# DashCam_Schematic.net
KiCad netlist of a schematic drawn in EAGLE
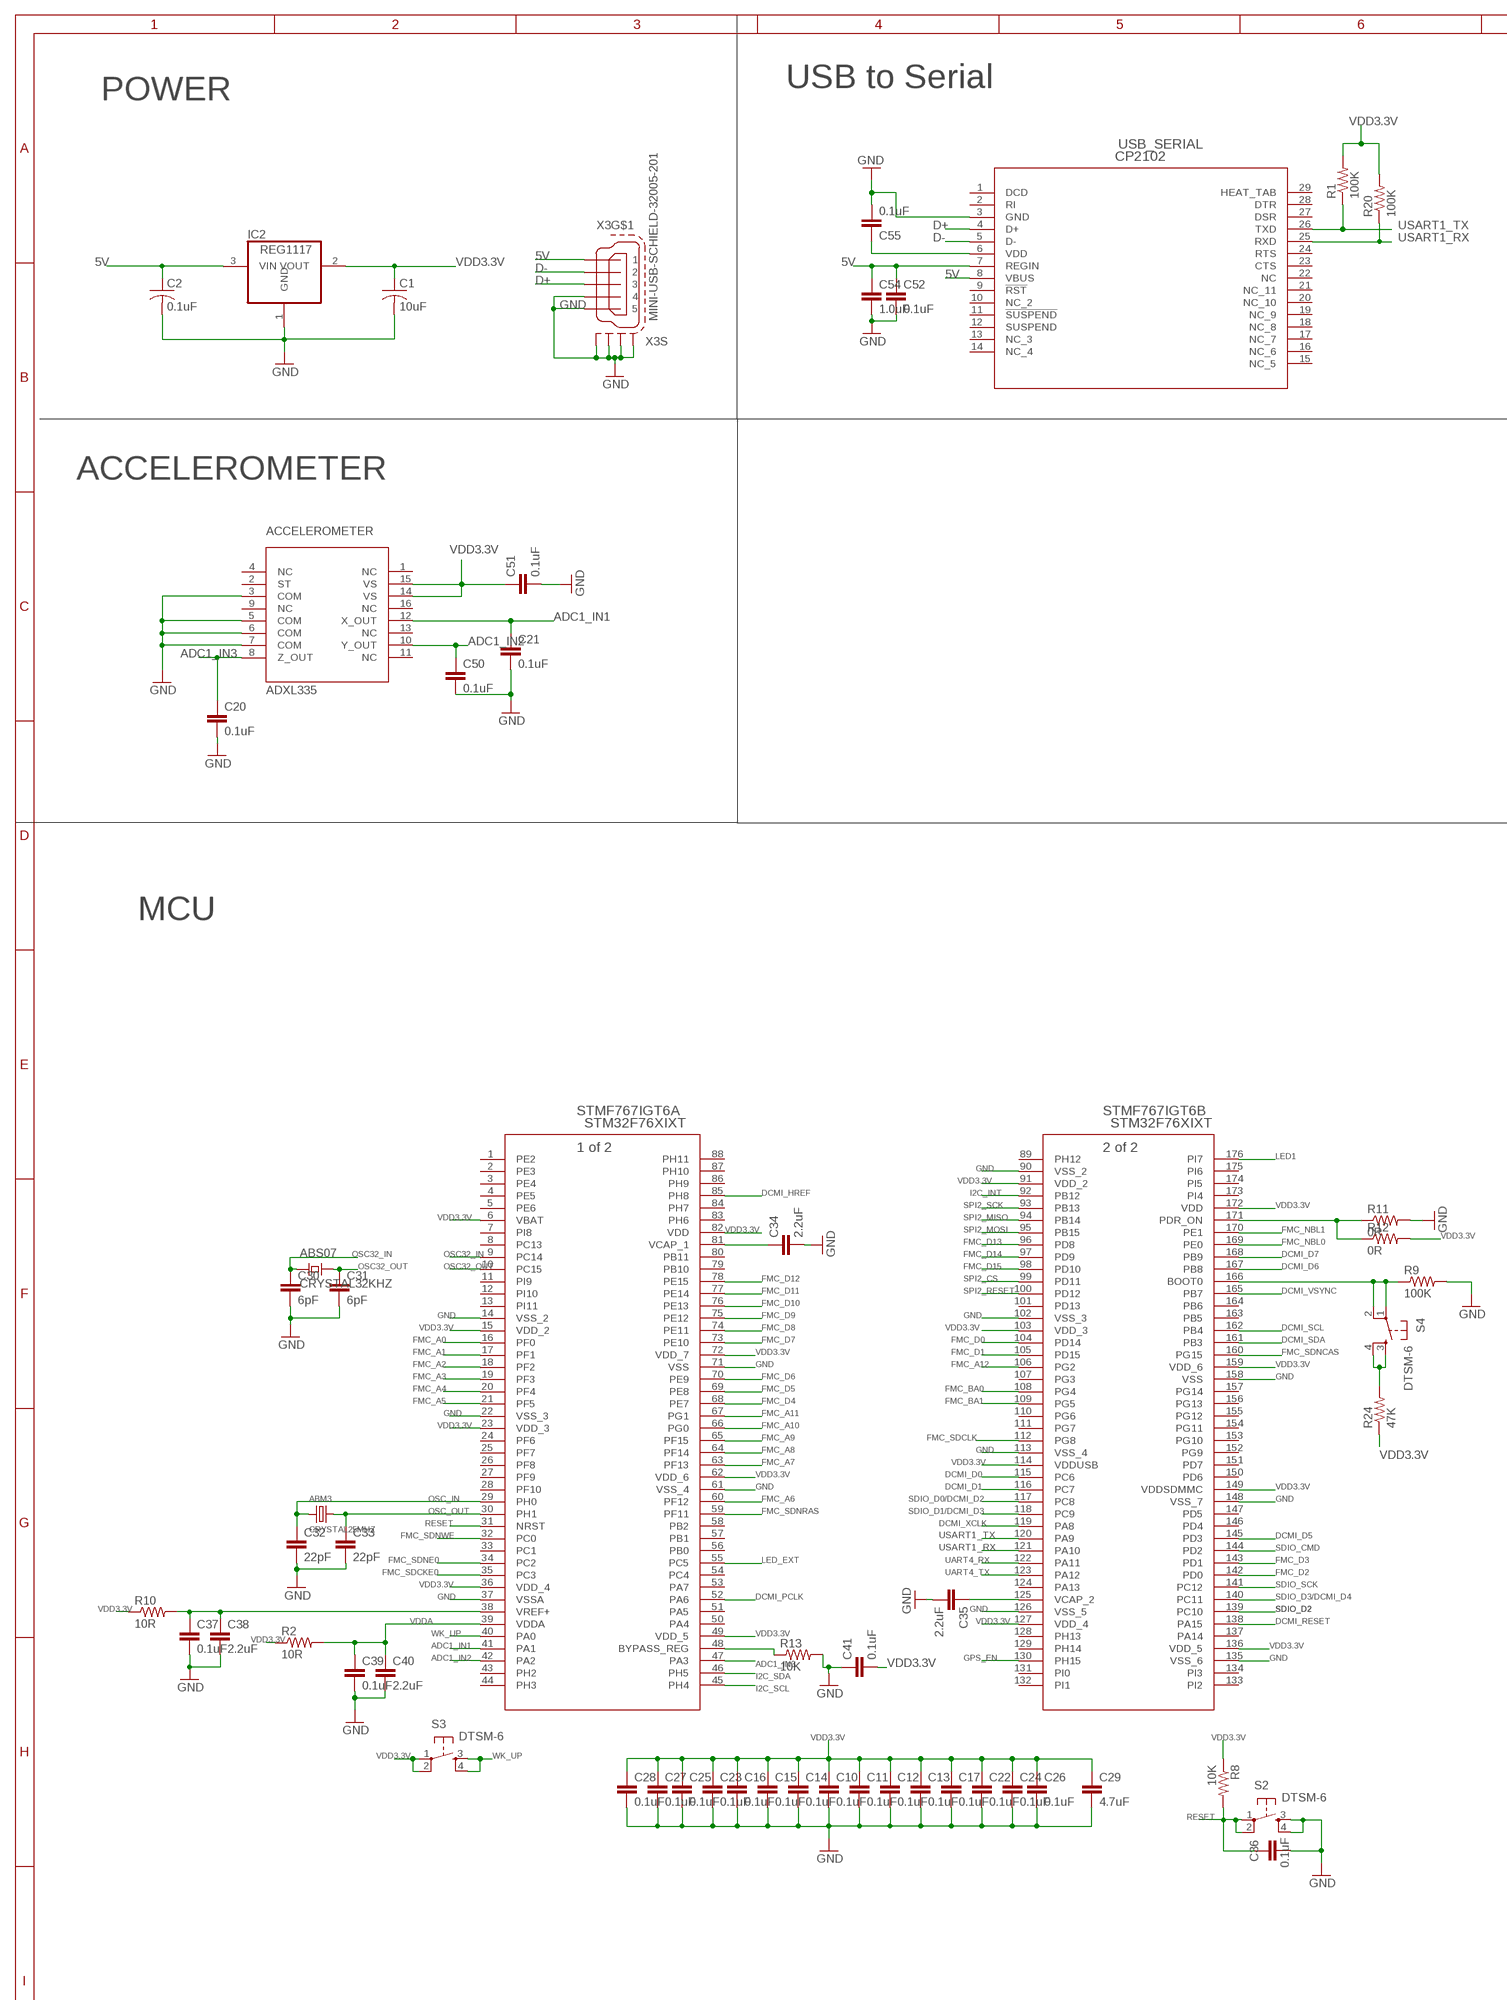
[diagram p0: schematic, sheet 1, part 1 of 2]
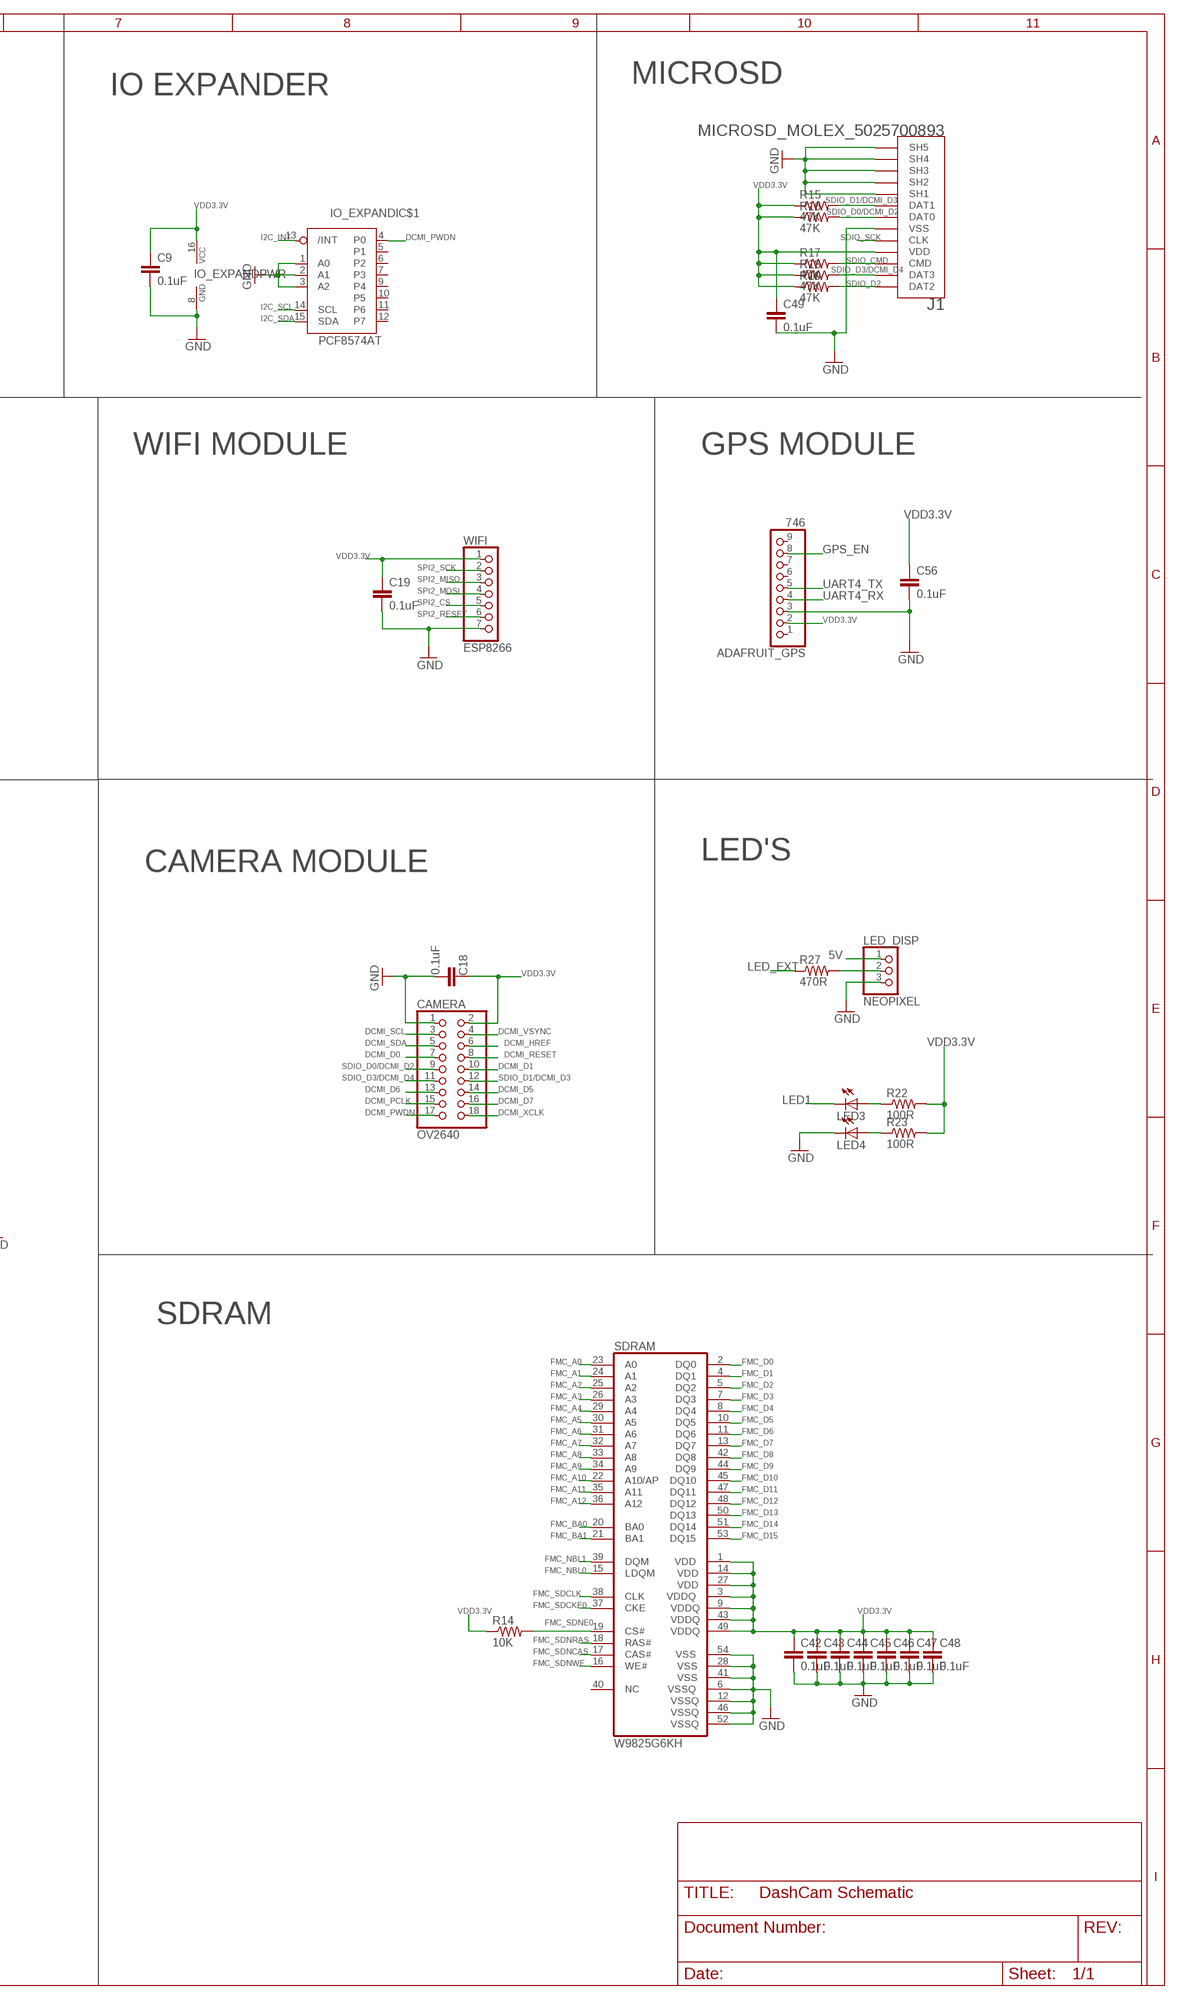
[diagram p1: schematic, sheet 1, part 2 of 2]

(export (version "E")
  (design (tool "Eeschema 10.0.6"))
  (components
    (comp (ref "ABM3")
      (value "CRYSTAL25MHZ")
      (footprint "eagle-import:6X3.3MM")
      (libsource (lib "eagle-import") (part "CRYSTAL.6X3.3MM"))
    )
    (comp (ref "ABS07")
      (value "CRYSTAL32KHZ")
      (footprint "eagle-import:2-SMD_ABM7")
      (libsource (lib "eagle-import") (part "ABSO7"))
    )
    (comp (ref "ACCELEROMETER")
      (value "ADXL335")
      (footprint "eagle-import:LFCSP16")
      (libsource (lib "eagle-import") (part "ADXL335"))
    )
    (comp (ref "ADAFRUIT_GPS")
      (value "746")
      (footprint "eagle-import:1X09")
      (libsource (lib "eagle-import") (part "PINHD-1X9"))
    )
    (comp (ref "C1")
      (value "10uF")
      (footprint "eagle-import:C0805")
      (libsource (lib "eagle-import") (part "C-USC0805"))
    )
    (comp (ref "C2")
      (value "0.1uF")
      (footprint "eagle-import:C0402")
      (libsource (lib "eagle-import") (part "C-USC0402"))
    )
    (comp (ref "C9")
      (value "0.1uF")
      (footprint "eagle-import:C0402")
      (libsource (lib "eagle-import") (part "C-EUC0402"))
    )
    (comp (ref "C10")
      (value "0.1uF")
      (footprint "eagle-import:C0402")
      (libsource (lib "eagle-import") (part "C-EUC0402"))
    )
    (comp (ref "C11")
      (value "0.1uF")
      (footprint "eagle-import:C0402")
      (libsource (lib "eagle-import") (part "C-EUC0402"))
    )
    (comp (ref "C12")
      (value "0.1uF")
      (footprint "eagle-import:C0402")
      (libsource (lib "eagle-import") (part "C-EUC0402"))
    )
    (comp (ref "C13")
      (value "0.1uF")
      (footprint "eagle-import:C0402")
      (libsource (lib "eagle-import") (part "C-EUC0402"))
    )
    (comp (ref "C14")
      (value "0.1uF")
      (footprint "eagle-import:C0402")
      (libsource (lib "eagle-import") (part "C-EUC0402"))
    )
    (comp (ref "C15")
      (value "0.1uF")
      (footprint "eagle-import:C0402")
      (libsource (lib "eagle-import") (part "C-EUC0402"))
    )
    (comp (ref "C16")
      (value "0.1uF")
      (footprint "eagle-import:C0402")
      (libsource (lib "eagle-import") (part "C-EUC0402"))
    )
    (comp (ref "C17")
      (value "0.1uF")
      (footprint "eagle-import:C0402")
      (libsource (lib "eagle-import") (part "C-EUC0402"))
    )
    (comp (ref "C18")
      (value "0.1uF")
      (footprint "eagle-import:C0402")
      (libsource (lib "eagle-import") (part "C-EUC0402"))
    )
    (comp (ref "C19")
      (value "0.1uF")
      (footprint "eagle-import:C0402")
      (libsource (lib "eagle-import") (part "C-EUC0402"))
    )
    (comp (ref "C20")
      (value "0.1uF")
      (footprint "eagle-import:C0402")
      (libsource (lib "eagle-import") (part "C-EUC0402"))
    )
    (comp (ref "C21")
      (value "0.1uF")
      (footprint "eagle-import:C0402")
      (libsource (lib "eagle-import") (part "C-EUC0402"))
    )
    (comp (ref "C22")
      (value "0.1uF")
      (footprint "eagle-import:C0402")
      (libsource (lib "eagle-import") (part "C-EUC0402"))
    )
    (comp (ref "C23")
      (value "0.1uF")
      (footprint "eagle-import:C0402")
      (libsource (lib "eagle-import") (part "C-EUC0402"))
    )
    (comp (ref "C24")
      (value "0.1uF")
      (footprint "eagle-import:C0402")
      (libsource (lib "eagle-import") (part "C-EUC0402"))
    )
    (comp (ref "C25")
      (value "0.1uF")
      (footprint "eagle-import:C0402")
      (libsource (lib "eagle-import") (part "C-EUC0402"))
    )
    (comp (ref "C26")
      (value "0.1uF")
      (footprint "eagle-import:C0402")
      (libsource (lib "eagle-import") (part "C-EUC0402"))
    )
    (comp (ref "C27")
      (value "0.1uF")
      (footprint "eagle-import:C0402")
      (libsource (lib "eagle-import") (part "C-EUC0402"))
    )
    (comp (ref "C28")
      (value "0.1uF")
      (footprint "eagle-import:C0402")
      (libsource (lib "eagle-import") (part "C-EUC0402"))
    )
    (comp (ref "C29")
      (value "4.7uF")
      (footprint "eagle-import:C0603")
      (libsource (lib "eagle-import") (part "C-EUC0603"))
    )
    (comp (ref "C30")
      (value "6pF")
      (footprint "eagle-import:C0402")
      (libsource (lib "eagle-import") (part "C-EUC0402"))
    )
    (comp (ref "C31")
      (value "6pF")
      (footprint "eagle-import:C0402")
      (libsource (lib "eagle-import") (part "C-EUC0402"))
    )
    (comp (ref "C32")
      (value "22pF")
      (footprint "eagle-import:C0201")
      (libsource (lib "eagle-import") (part "C-EUC0201"))
    )
    (comp (ref "C33")
      (value "22pF")
      (footprint "eagle-import:C0201")
      (libsource (lib "eagle-import") (part "C-EUC0201"))
    )
    (comp (ref "C34")
      (value "2.2uF")
      (footprint "eagle-import:C0805")
      (libsource (lib "eagle-import") (part "C-EUC0805"))
    )
    (comp (ref "C35")
      (value "2.2uF")
      (footprint "eagle-import:C0805")
      (libsource (lib "eagle-import") (part "C-EUC0805"))
    )
    (comp (ref "C36")
      (value "0.1uF")
      (footprint "eagle-import:C0402")
      (libsource (lib "eagle-import") (part "C-EUC0402"))
    )
    (comp (ref "C37")
      (value "0.1uF")
      (footprint "eagle-import:C0402")
      (libsource (lib "eagle-import") (part "C-EUC0402"))
    )
    (comp (ref "C38")
      (value "2.2uF")
      (footprint "eagle-import:C0805")
      (libsource (lib "eagle-import") (part "C-EUC0805"))
    )
    (comp (ref "C39")
      (value "0.1uF")
      (footprint "eagle-import:C0402")
      (libsource (lib "eagle-import") (part "C-EUC0402"))
    )
    (comp (ref "C40")
      (value "2.2uF")
      (footprint "eagle-import:C0805")
      (libsource (lib "eagle-import") (part "C-EUC0805"))
    )
    (comp (ref "C41")
      (value "0.1uF")
      (footprint "eagle-import:C0402")
      (libsource (lib "eagle-import") (part "C-EUC0402"))
    )
    (comp (ref "C42")
      (value "0.1uF")
      (footprint "eagle-import:C0402")
      (libsource (lib "eagle-import") (part "C-EUC0402"))
    )
    (comp (ref "C43")
      (value "0.1uF")
      (footprint "eagle-import:C0402")
      (libsource (lib "eagle-import") (part "C-EUC0402"))
    )
    (comp (ref "C44")
      (value "0.1uF")
      (footprint "eagle-import:C0402")
      (libsource (lib "eagle-import") (part "C-EUC0402"))
    )
    (comp (ref "C45")
      (value "0.1uF")
      (footprint "eagle-import:C0402")
      (libsource (lib "eagle-import") (part "C-EUC0402"))
    )
    (comp (ref "C46")
      (value "0.1uF")
      (footprint "eagle-import:C0402")
      (libsource (lib "eagle-import") (part "C-EUC0402"))
    )
    (comp (ref "C47")
      (value "0.1uF")
      (footprint "eagle-import:C0402")
      (libsource (lib "eagle-import") (part "C-EUC0402"))
    )
    (comp (ref "C48")
      (value "0.1uF")
      (footprint "eagle-import:C0402")
      (libsource (lib "eagle-import") (part "C-EUC0402"))
    )
    (comp (ref "C49")
      (value "0.1uF")
      (footprint "eagle-import:C0402")
      (libsource (lib "eagle-import") (part "C-EUC0402"))
    )
    (comp (ref "C50")
      (value "0.1uF")
      (footprint "eagle-import:C0402")
      (libsource (lib "eagle-import") (part "C-EUC0402"))
    )
    (comp (ref "C51")
      (value "0.1uF")
      (footprint "eagle-import:C0402")
      (libsource (lib "eagle-import") (part "C-EUC0402"))
    )
    (comp (ref "C52")
      (value "0.1uF")
      (footprint "eagle-import:C0402")
      (libsource (lib "eagle-import") (part "C-EUC0402"))
    )
    (comp (ref "C54")
      (value "1.0uF")
      (footprint "eagle-import:C0402")
      (libsource (lib "eagle-import") (part "C-EUC0402"))
    )
    (comp (ref "C55")
      (value "0.1uF")
      (footprint "eagle-import:C0402")
      (libsource (lib "eagle-import") (part "C-EUC0402"))
    )
    (comp (ref "C56")
      (value "0.1uF")
      (footprint "eagle-import:C0402")
      (libsource (lib "eagle-import") (part "C-EUC0402"))
    )
    (comp (ref "CAMERA")
      (value "OV2640")
      (footprint "eagle-import:2X09_90")
      (libsource (lib "eagle-import") (part "PINHD-2X9/90"))
    )
    (comp (ref "IC2")
      (value "REG1117")
      (footprint "eagle-import:SOT223")
      (libsource (lib "eagle-import") (part "REG1117"))
    )
    (comp (ref "IO_EXPAND")
      (value "PCF8574AT")
      (footprint "eagle-import:SO16")
      (libsource (lib "eagle-import") (part "PCF8574AT"))
    )
    (comp (ref "J1")
      (value "MICROSD_MOLEX_5025700893")
      (footprint "eagle-import:5025700893")
      (libsource (lib "eagle-import") (part "MICROSD_MOLEX_5025700893"))
    )
    (comp (ref "LED3")
      (value "LEDCHIP-LED0603")
      (footprint "eagle-import:CHIP-LED0603")
      (libsource (lib "eagle-import") (part "LEDCHIP-LED0603"))
    )
    (comp (ref "LED4")
      (value "LEDCHIP-LED0603")
      (footprint "eagle-import:CHIP-LED0603")
      (libsource (lib "eagle-import") (part "LEDCHIP-LED0603"))
    )
    (comp (ref "LED_DISP")
      (value "NEOPIXEL")
      (footprint "eagle-import:1X03")
      (libsource (lib "eagle-import") (part "PINHD-1X3"))
    )
    (comp (ref "R1")
      (value "100K")
      (footprint "eagle-import:R0805")
      (libsource (lib "eagle-import") (part "R-US_R0805"))
    )
    (comp (ref "R2")
      (value "10R")
      (footprint "eagle-import:R0603")
      (libsource (lib "eagle-import") (part "R-US_R0603"))
    )
    (comp (ref "R8")
      (value "10K")
      (footprint "eagle-import:R0402")
      (libsource (lib "eagle-import") (part "R-US_R0402"))
    )
    (comp (ref "R9")
      (value "100K")
      (footprint "eagle-import:R0805")
      (libsource (lib "eagle-import") (part "R-US_R0805"))
    )
    (comp (ref "R10")
      (value "10R")
      (footprint "eagle-import:R0603")
      (libsource (lib "eagle-import") (part "R-US_R0603"))
    )
    (comp (ref "R11")
      (value "0R")
      (footprint "eagle-import:R0402")
      (libsource (lib "eagle-import") (part "R-US_R0402"))
    )
    (comp (ref "R12")
      (value "0R")
      (footprint "eagle-import:R0402")
      (libsource (lib "eagle-import") (part "R-US_R0402"))
    )
    (comp (ref "R13")
      (value "10K")
      (footprint "eagle-import:R0402")
      (libsource (lib "eagle-import") (part "R-US_R0402"))
    )
    (comp (ref "R14")
      (value "10K")
      (footprint "eagle-import:R0402")
      (libsource (lib "eagle-import") (part "R-US_R0402"))
    )
    (comp (ref "R15")
      (value "47K")
      (footprint "eagle-import:R0402")
      (libsource (lib "eagle-import") (part "R-US_R0402"))
    )
    (comp (ref "R16")
      (value "47K")
      (footprint "eagle-import:R0402")
      (libsource (lib "eagle-import") (part "R-US_R0402"))
    )
    (comp (ref "R17")
      (value "47K")
      (footprint "eagle-import:R0402")
      (libsource (lib "eagle-import") (part "R-US_R0402"))
    )
    (comp (ref "R18")
      (value "47K")
      (footprint "eagle-import:R0402")
      (libsource (lib "eagle-import") (part "R-US_R0402"))
    )
    (comp (ref "R19")
      (value "47K")
      (footprint "eagle-import:R0402")
      (libsource (lib "eagle-import") (part "R-US_R0402"))
    )
    (comp (ref "R20")
      (value "100K")
      (footprint "eagle-import:R0805")
      (libsource (lib "eagle-import") (part "R-US_R0805"))
    )
    (comp (ref "R22")
      (value "100R")
      (footprint "eagle-import:R0402")
      (libsource (lib "eagle-import") (part "R-US_R0402"))
    )
    (comp (ref "R23")
      (value "100R")
      (footprint "eagle-import:R0402")
      (libsource (lib "eagle-import") (part "R-US_R0402"))
    )
    (comp (ref "R24")
      (value "47K")
      (footprint "eagle-import:R0402")
      (libsource (lib "eagle-import") (part "R-US_R0402"))
    )
    (comp (ref "R27")
      (value "470R")
      (footprint "eagle-import:R0603")
      (libsource (lib "eagle-import") (part "R-US_R0603"))
    )
    (comp (ref "S2")
      (value "DTSM-6")
      (footprint "eagle-import:DTSM-6")
      (libsource (lib "eagle-import") (part "DTSM-6"))
    )
    (comp (ref "S3")
      (value "DTSM-6")
      (footprint "eagle-import:DTSM-6")
      (libsource (lib "eagle-import") (part "DTSM-6"))
    )
    (comp (ref "S4")
      (value "DTSM-6")
      (footprint "eagle-import:DTSM-6")
      (libsource (lib "eagle-import") (part "DTSM-6"))
    )
    (comp (ref "SDRAM")
      (value "W9825G6KH")
      (footprint "eagle-import:TSOP54")
      (libsource (lib "eagle-import") (part "K4S561632E-TC"))
    )
    (comp (ref "STMF767IGT6")
      (value "STM32F76XIXT")
      (footprint "eagle-import:LQFP-176_24X24")
      (libsource (lib "eagle-import") (part "STM32F76XIXT"))
    )
    (comp (ref "USB_SERIAL")
      (value "CP2102")
      (footprint "eagle-import:QFN28N5X5-0P5P")
      (libsource (lib "eagle-import") (part "CP2102"))
    )
    (comp (ref "WIFI")
      (value "ESP8266")
      (footprint "eagle-import:1X07")
      (libsource (lib "eagle-import") (part "PINHD-1X7"))
    )
    (comp (ref "X3")
      (value "MINI-USB-SCHIELD-32005-201")
      (footprint "eagle-import:32005-201")
      (libsource (lib "eagle-import") (part "MINI-USB-SCHIELD-32005-201"))
    )
  )
  (nets
    (net (code "1") (name "/5V") (class "Default")
      (node (ref "C2") (pin "1") (pinfunction "1_1") (pintype "passive"))
      (node (ref "C52") (pin "1") (pinfunction "1_1") (pintype "passive"))
      (node (ref "C54") (pin "1") (pinfunction "1_1") (pintype "passive"))
      (node (ref "IC2") (pin "3") (pinfunction "VIN_3") (pintype "input"))
      (node (ref "LED_DISP") (pin "1") (pinfunction "1_1") (pintype "passive"))
      (node (ref "USB_SERIAL") (pin "7") (pinfunction "REGIN_7") (pintype "passive"))
      (node (ref "USB_SERIAL") (pin "8") (pinfunction "VBUS_8") (pintype "passive"))
      (node (ref "X3") (pin "1") (pinfunction "1_1") (pintype "passive"))
    )
    (net (code "2") (name "/ADC1_IN1") (class "Default")
      (node (ref "ACCELEROMETER") (pin "12") (pinfunction "X_OUT_12") (pintype "bidirectional"))
      (node (ref "C21") (pin "1") (pinfunction "1_1") (pintype "passive"))
      (node (ref "STMF767IGT6") (pin "41") (pinfunction "PA1_41") (pintype "bidirectional"))
    )
    (net (code "3") (name "/ADC1_IN2") (class "Default")
      (node (ref "ACCELEROMETER") (pin "10") (pinfunction "Y_OUT_10") (pintype "bidirectional"))
      (node (ref "C50") (pin "1") (pinfunction "1_1") (pintype "passive"))
      (node (ref "STMF767IGT6") (pin "42") (pinfunction "PA2_42") (pintype "bidirectional"))
    )
    (net (code "4") (name "/ADC1_IN3") (class "Default")
      (node (ref "ACCELEROMETER") (pin "8") (pinfunction "Z_OUT_8") (pintype "bidirectional"))
      (node (ref "C20") (pin "1") (pinfunction "1_1") (pintype "passive"))
      (node (ref "STMF767IGT6") (pin "47") (pinfunction "PA3_47") (pintype "bidirectional"))
    )
    (net (code "5") (name "/D+") (class "Default")
      (node (ref "USB_SERIAL") (pin "4") (pinfunction "D+_4") (pintype "passive"))
      (node (ref "X3") (pin "3") (pinfunction "3_3") (pintype "passive"))
    )
    (net (code "6") (name "/D-") (class "Default")
      (node (ref "USB_SERIAL") (pin "5") (pinfunction "D-_5") (pintype "passive"))
      (node (ref "X3") (pin "2") (pinfunction "2_2") (pintype "passive"))
    )
    (net (code "7") (name "/DCMI_D0") (class "Default")
      (node (ref "CAMERA") (pin "7") (pinfunction "7_7") (pintype "passive"))
      (node (ref "STMF767IGT6") (pin "115") (pinfunction "PC6_115") (pintype "bidirectional"))
    )
    (net (code "8") (name "/DCMI_D1") (class "Default")
      (node (ref "CAMERA") (pin "10") (pinfunction "10_10") (pintype "passive"))
      (node (ref "STMF767IGT6") (pin "116") (pinfunction "PC7_116") (pintype "bidirectional"))
    )
    (net (code "9") (name "/DCMI_D5") (class "Default")
      (node (ref "CAMERA") (pin "14") (pinfunction "14_14") (pintype "passive"))
      (node (ref "STMF767IGT6") (pin "145") (pinfunction "PD3_145") (pintype "bidirectional"))
    )
    (net (code "10") (name "/DCMI_D6") (class "Default")
      (node (ref "CAMERA") (pin "13") (pinfunction "13_13") (pintype "passive"))
      (node (ref "STMF767IGT6") (pin "167") (pinfunction "PB8_167") (pintype "bidirectional"))
    )
    (net (code "11") (name "/DCMI_D7") (class "Default")
      (node (ref "CAMERA") (pin "16") (pinfunction "16_16") (pintype "passive"))
      (node (ref "STMF767IGT6") (pin "168") (pinfunction "PB9_168") (pintype "bidirectional"))
    )
    (net (code "12") (name "/DCMI_HREF") (class "Default")
      (node (ref "CAMERA") (pin "6") (pinfunction "6_6") (pintype "passive"))
      (node (ref "STMF767IGT6") (pin "85") (pinfunction "PH8_85") (pintype "bidirectional"))
    )
    (net (code "13") (name "/DCMI_PCLK") (class "Default")
      (node (ref "CAMERA") (pin "15") (pinfunction "15_15") (pintype "passive"))
      (node (ref "STMF767IGT6") (pin "52") (pinfunction "PA6_52") (pintype "bidirectional"))
    )
    (net (code "14") (name "/DCMI_PWDN") (class "Default")
      (node (ref "CAMERA") (pin "17") (pinfunction "17_17") (pintype "passive"))
      (node (ref "IO_EXPAND") (pin "4") (pinfunction "P0_4") (pintype "bidirectional"))
    )
    (net (code "15") (name "/DCMI_RESET") (class "Default")
      (node (ref "CAMERA") (pin "8") (pinfunction "8_8") (pintype "passive"))
      (node (ref "STMF767IGT6") (pin "138") (pinfunction "PA15_138") (pintype "bidirectional"))
    )
    (net (code "16") (name "/DCMI_SCL") (class "Default")
      (node (ref "CAMERA") (pin "3") (pinfunction "3_3") (pintype "passive"))
      (node (ref "STMF767IGT6") (pin "162") (pinfunction "PB4_162") (pintype "bidirectional"))
    )
    (net (code "17") (name "/DCMI_SDA") (class "Default")
      (node (ref "CAMERA") (pin "5") (pinfunction "5_5") (pintype "passive"))
      (node (ref "STMF767IGT6") (pin "161") (pinfunction "PB3_161") (pintype "bidirectional"))
    )
    (net (code "18") (name "/DCMI_VSYNC") (class "Default")
      (node (ref "CAMERA") (pin "4") (pinfunction "4_4") (pintype "passive"))
      (node (ref "STMF767IGT6") (pin "165") (pinfunction "PB7_165") (pintype "bidirectional"))
    )
    (net (code "19") (name "/DCMI_XCLK") (class "Default")
      (node (ref "CAMERA") (pin "18") (pinfunction "18_18") (pintype "passive"))
      (node (ref "STMF767IGT6") (pin "119") (pinfunction "PA8_119") (pintype "bidirectional"))
    )
    (net (code "20") (name "/FMC_A0") (class "Default")
      (node (ref "SDRAM") (pin "23") (pinfunction "A0_23") (pintype "input"))
      (node (ref "STMF767IGT6") (pin "16") (pinfunction "PF0_16") (pintype "bidirectional"))
    )
    (net (code "21") (name "/FMC_A1") (class "Default")
      (node (ref "SDRAM") (pin "24") (pinfunction "A1_24") (pintype "input"))
      (node (ref "STMF767IGT6") (pin "17") (pinfunction "PF1_17") (pintype "bidirectional"))
    )
    (net (code "22") (name "/FMC_A2") (class "Default")
      (node (ref "SDRAM") (pin "25") (pinfunction "A2_25") (pintype "input"))
      (node (ref "STMF767IGT6") (pin "18") (pinfunction "PF2_18") (pintype "bidirectional"))
    )
    (net (code "23") (name "/FMC_A3") (class "Default")
      (node (ref "SDRAM") (pin "26") (pinfunction "A3_26") (pintype "input"))
      (node (ref "STMF767IGT6") (pin "19") (pinfunction "PF3_19") (pintype "bidirectional"))
    )
    (net (code "24") (name "/FMC_A4") (class "Default")
      (node (ref "SDRAM") (pin "29") (pinfunction "A4_29") (pintype "input"))
      (node (ref "STMF767IGT6") (pin "20") (pinfunction "PF4_20") (pintype "bidirectional"))
    )
    (net (code "25") (name "/FMC_A5") (class "Default")
      (node (ref "SDRAM") (pin "30") (pinfunction "A5_30") (pintype "input"))
      (node (ref "STMF767IGT6") (pin "21") (pinfunction "PF5_21") (pintype "bidirectional"))
    )
    (net (code "26") (name "/FMC_A6") (class "Default")
      (node (ref "SDRAM") (pin "31") (pinfunction "A6_31") (pintype "input"))
      (node (ref "STMF767IGT6") (pin "60") (pinfunction "PF12_60") (pintype "bidirectional"))
    )
    (net (code "27") (name "/FMC_A7") (class "Default")
      (node (ref "SDRAM") (pin "32") (pinfunction "A7_32") (pintype "input"))
      (node (ref "STMF767IGT6") (pin "63") (pinfunction "PF13_63") (pintype "bidirectional"))
    )
    (net (code "28") (name "/FMC_A8") (class "Default")
      (node (ref "SDRAM") (pin "33") (pinfunction "A8_33") (pintype "input"))
      (node (ref "STMF767IGT6") (pin "64") (pinfunction "PF14_64") (pintype "bidirectional"))
    )
    (net (code "29") (name "/FMC_A9") (class "Default")
      (node (ref "SDRAM") (pin "34") (pinfunction "A9_34") (pintype "input"))
      (node (ref "STMF767IGT6") (pin "65") (pinfunction "PF15_65") (pintype "bidirectional"))
    )
    (net (code "30") (name "/FMC_A10") (class "Default")
      (node (ref "SDRAM") (pin "22") (pinfunction "A10/AP_22") (pintype "input"))
      (node (ref "STMF767IGT6") (pin "66") (pinfunction "PG0_66") (pintype "bidirectional"))
    )
    (net (code "31") (name "/FMC_A11") (class "Default")
      (node (ref "SDRAM") (pin "35") (pinfunction "A11_35") (pintype "input"))
      (node (ref "STMF767IGT6") (pin "67") (pinfunction "PG1_67") (pintype "bidirectional"))
    )
    (net (code "32") (name "/FMC_A12") (class "Default")
      (node (ref "SDRAM") (pin "36") (pinfunction "A12_36") (pintype "input"))
      (node (ref "STMF767IGT6") (pin "106") (pinfunction "PG2_106") (pintype "bidirectional"))
    )
    (net (code "33") (name "/FMC_BA0") (class "Default")
      (node (ref "SDRAM") (pin "20") (pinfunction "BA0_20") (pintype "input"))
      (node (ref "STMF767IGT6") (pin "108") (pinfunction "PG4_108") (pintype "bidirectional"))
    )
    (net (code "34") (name "/FMC_BA1") (class "Default")
      (node (ref "SDRAM") (pin "21") (pinfunction "BA1_21") (pintype "input"))
      (node (ref "STMF767IGT6") (pin "109") (pinfunction "PG5_109") (pintype "bidirectional"))
    )
    (net (code "35") (name "/FMC_D0") (class "Default")
      (node (ref "SDRAM") (pin "2") (pinfunction "DQ0_2") (pintype "bidirectional"))
      (node (ref "STMF767IGT6") (pin "104") (pinfunction "PD14_104") (pintype "bidirectional"))
    )
    (net (code "36") (name "/FMC_D1") (class "Default")
      (node (ref "SDRAM") (pin "4") (pinfunction "DQ1_4") (pintype "bidirectional"))
      (node (ref "STMF767IGT6") (pin "105") (pinfunction "PD15_105") (pintype "bidirectional"))
    )
    (net (code "37") (name "/FMC_D2") (class "Default")
      (node (ref "SDRAM") (pin "5") (pinfunction "DQ2_5") (pintype "bidirectional"))
      (node (ref "STMF767IGT6") (pin "142") (pinfunction "PD0_142") (pintype "bidirectional"))
    )
    (net (code "38") (name "/FMC_D3") (class "Default")
      (node (ref "SDRAM") (pin "7") (pinfunction "DQ3_7") (pintype "bidirectional"))
      (node (ref "STMF767IGT6") (pin "143") (pinfunction "PD1_143") (pintype "bidirectional"))
    )
    (net (code "39") (name "/FMC_D4") (class "Default")
      (node (ref "SDRAM") (pin "8") (pinfunction "DQ4_8") (pintype "bidirectional"))
      (node (ref "STMF767IGT6") (pin "68") (pinfunction "PE7_68") (pintype "bidirectional"))
    )
    (net (code "40") (name "/FMC_D5") (class "Default")
      (node (ref "SDRAM") (pin "10") (pinfunction "DQ5_10") (pintype "bidirectional"))
      (node (ref "STMF767IGT6") (pin "69") (pinfunction "PE8_69") (pintype "bidirectional"))
    )
    (net (code "41") (name "/FMC_D6") (class "Default")
      (node (ref "SDRAM") (pin "11") (pinfunction "DQ6_11") (pintype "bidirectional"))
      (node (ref "STMF767IGT6") (pin "70") (pinfunction "PE9_70") (pintype "bidirectional"))
    )
    (net (code "42") (name "/FMC_D7") (class "Default")
      (node (ref "SDRAM") (pin "13") (pinfunction "DQ7_13") (pintype "bidirectional"))
      (node (ref "STMF767IGT6") (pin "73") (pinfunction "PE10_73") (pintype "bidirectional"))
    )
    (net (code "43") (name "/FMC_D8") (class "Default")
      (node (ref "SDRAM") (pin "42") (pinfunction "DQ8_42") (pintype "bidirectional"))
      (node (ref "STMF767IGT6") (pin "74") (pinfunction "PE11_74") (pintype "bidirectional"))
    )
    (net (code "44") (name "/FMC_D9") (class "Default")
      (node (ref "SDRAM") (pin "44") (pinfunction "DQ9_44") (pintype "bidirectional"))
      (node (ref "STMF767IGT6") (pin "75") (pinfunction "PE12_75") (pintype "bidirectional"))
    )
    (net (code "45") (name "/FMC_D10") (class "Default")
      (node (ref "SDRAM") (pin "45") (pinfunction "DQ10_45") (pintype "bidirectional"))
      (node (ref "STMF767IGT6") (pin "76") (pinfunction "PE13_76") (pintype "bidirectional"))
    )
    (net (code "46") (name "/FMC_D11") (class "Default")
      (node (ref "SDRAM") (pin "47") (pinfunction "DQ11_47") (pintype "bidirectional"))
      (node (ref "STMF767IGT6") (pin "77") (pinfunction "PE14_77") (pintype "bidirectional"))
    )
    (net (code "47") (name "/FMC_D12") (class "Default")
      (node (ref "SDRAM") (pin "48") (pinfunction "DQ12_48") (pintype "bidirectional"))
      (node (ref "STMF767IGT6") (pin "78") (pinfunction "PE15_78") (pintype "bidirectional"))
    )
    (net (code "48") (name "/FMC_D13") (class "Default")
      (node (ref "SDRAM") (pin "50") (pinfunction "DQ13_50") (pintype "bidirectional"))
      (node (ref "STMF767IGT6") (pin "96") (pinfunction "PD8_96") (pintype "bidirectional"))
    )
    (net (code "49") (name "/FMC_D14") (class "Default")
      (node (ref "SDRAM") (pin "51") (pinfunction "DQ14_51") (pintype "bidirectional"))
      (node (ref "STMF767IGT6") (pin "97") (pinfunction "PD9_97") (pintype "bidirectional"))
    )
    (net (code "50") (name "/FMC_D15") (class "Default")
      (node (ref "SDRAM") (pin "53") (pinfunction "DQ15_53") (pintype "bidirectional"))
      (node (ref "STMF767IGT6") (pin "98") (pinfunction "PD10_98") (pintype "bidirectional"))
    )
    (net (code "51") (name "/FMC_NBL0") (class "Default")
      (node (ref "SDRAM") (pin "15") (pinfunction "LDQM_15") (pintype "input"))
      (node (ref "STMF767IGT6") (pin "169") (pinfunction "PE0_169") (pintype "bidirectional"))
    )
    (net (code "52") (name "/FMC_NBL1") (class "Default")
      (node (ref "SDRAM") (pin "39") (pinfunction "DQM_39") (pintype "input"))
      (node (ref "STMF767IGT6") (pin "170") (pinfunction "PE1_170") (pintype "bidirectional"))
    )
    (net (code "53") (name "/FMC_SDCKE0") (class "Default")
      (node (ref "SDRAM") (pin "37") (pinfunction "CKE_37") (pintype "input"))
      (node (ref "STMF767IGT6") (pin "35") (pinfunction "PC3_35") (pintype "bidirectional"))
    )
    (net (code "54") (name "/FMC_SDCLK") (class "Default")
      (node (ref "SDRAM") (pin "38") (pinfunction "CLK_38") (pintype "input"))
      (node (ref "STMF767IGT6") (pin "112") (pinfunction "PG8_112") (pintype "bidirectional"))
    )
    (net (code "55") (name "/FMC_SDNCAS") (class "Default")
      (node (ref "SDRAM") (pin "17") (pinfunction "CAS#_17") (pintype "input"))
      (node (ref "STMF767IGT6") (pin "160") (pinfunction "PG15_160") (pintype "bidirectional"))
    )
    (net (code "56") (name "/FMC_SDNE0") (class "Default")
      (node (ref "R14") (pin "2") (pinfunction "2_2") (pintype "passive"))
      (node (ref "SDRAM") (pin "19") (pinfunction "CS#_19") (pintype "input"))
      (node (ref "STMF767IGT6") (pin "34") (pinfunction "PC2_34") (pintype "bidirectional"))
    )
    (net (code "57") (name "/FMC_SDNRAS") (class "Default")
      (node (ref "SDRAM") (pin "18") (pinfunction "RAS#_18") (pintype "input"))
      (node (ref "STMF767IGT6") (pin "59") (pinfunction "PF11_59") (pintype "bidirectional"))
    )
    (net (code "58") (name "/FMC_SDNWE") (class "Default")
      (node (ref "SDRAM") (pin "16") (pinfunction "WE#_16") (pintype "input"))
      (node (ref "STMF767IGT6") (pin "32") (pinfunction "PC0_32") (pintype "bidirectional"))
    )
    (net (code "59") (name "/GPS_EN") (class "Default")
      (node (ref "ADAFRUIT_GPS") (pin "8") (pinfunction "8_8") (pintype "passive"))
      (node (ref "STMF767IGT6") (pin "130") (pinfunction "PH15_130") (pintype "bidirectional"))
    )
    (net (code "60") (name "/I2C_INT") (class "Default")
      (node (ref "IO_EXPAND") (pin "13") (pinfunction "/INT_13") (pintype "output"))
      (node (ref "STMF767IGT6") (pin "92") (pinfunction "PB12_92") (pintype "bidirectional"))
    )
    (net (code "61") (name "/I2C_SCL") (class "Default")
      (node (ref "IO_EXPAND") (pin "14") (pinfunction "SCL_14") (pintype "input"))
      (node (ref "STMF767IGT6") (pin "45") (pinfunction "PH4_45") (pintype "bidirectional"))
    )
    (net (code "62") (name "/I2C_SDA") (class "Default")
      (node (ref "IO_EXPAND") (pin "15") (pinfunction "SDA_15") (pintype "bidirectional"))
      (node (ref "STMF767IGT6") (pin "46") (pinfunction "PH5_46") (pintype "bidirectional"))
    )
    (net (code "63") (name "/LED1") (class "Default")
      (node (ref "LED3") (pin "C") (pinfunction "C_C") (pintype "passive"))
      (node (ref "STMF767IGT6") (pin "176") (pinfunction "PI7_176") (pintype "bidirectional"))
    )
    (net (code "64") (name "/LED_EXT") (class "Default")
      (node (ref "R27") (pin "1") (pinfunction "1_1") (pintype "passive"))
      (node (ref "STMF767IGT6") (pin "55") (pinfunction "PC5_55") (pintype "bidirectional"))
    )
    (net (code "65") (name "/OSC32_IN") (class "Default")
      (node (ref "ABS07") (pin "P$1") (pinfunction "P$1_P$1") (pintype "bidirectional"))
      (node (ref "C30") (pin "1") (pinfunction "1_1") (pintype "passive"))
      (node (ref "STMF767IGT6") (pin "9") (pinfunction "PC14_9") (pintype "bidirectional"))
    )
    (net (code "66") (name "/OSC32_OUT") (class "Default")
      (node (ref "ABS07") (pin "P$2") (pinfunction "P$2_P$2") (pintype "bidirectional"))
      (node (ref "C31") (pin "1") (pinfunction "1_1") (pintype "passive"))
      (node (ref "STMF767IGT6") (pin "10") (pinfunction "PC15_10") (pintype "bidirectional"))
    )
    (net (code "67") (name "/OSC_IN") (class "Default")
      (node (ref "ABM3") (pin "1") (pinfunction "1_1") (pintype "passive"))
      (node (ref "C32") (pin "1") (pinfunction "1_1") (pintype "passive"))
      (node (ref "STMF767IGT6") (pin "29") (pinfunction "PH0_29") (pintype "bidirectional"))
    )
    (net (code "68") (name "/OSC_OUT") (class "Default")
      (node (ref "ABM3") (pin "2") (pinfunction "2_2") (pintype "passive"))
      (node (ref "C33") (pin "1") (pinfunction "1_1") (pintype "passive"))
      (node (ref "STMF767IGT6") (pin "30") (pinfunction "PH1_30") (pintype "bidirectional"))
    )
    (net (code "69") (name "/RESET") (class "Default")
      (node (ref "C36") (pin "1") (pinfunction "1_1") (pintype "passive"))
      (node (ref "R8") (pin "2") (pinfunction "2_2") (pintype "passive"))
      (node (ref "S2") (pin "1") (pinfunction "1_1") (pintype "passive"))
      (node (ref "S2") (pin "2") (pinfunction "2_2") (pintype "passive"))
      (node (ref "STMF767IGT6") (pin "31") (pinfunction "NRST_31") (pintype "bidirectional"))
    )
    (net (code "70") (name "/SDIO_CMD") (class "Default")
      (node (ref "J1") (pin "P$3") (pinfunction "CMD_P$3") (pintype "bidirectional"))
      (node (ref "R17") (pin "2") (pinfunction "2_2") (pintype "passive"))
      (node (ref "STMF767IGT6") (pin "144") (pinfunction "PD2_144") (pintype "bidirectional"))
    )
    (net (code "71") (name "/SDIO_D0{slash}DCMI_D2") (class "Default")
      (node (ref "CAMERA") (pin "9") (pinfunction "9_9") (pintype "passive"))
      (node (ref "J1") (pin "P$7") (pinfunction "DAT0_P$7") (pintype "bidirectional"))
      (node (ref "R16") (pin "2") (pinfunction "2_2") (pintype "passive"))
      (node (ref "STMF767IGT6") (pin "117") (pinfunction "PC8_117") (pintype "bidirectional"))
    )
    (net (code "72") (name "/SDIO_D1{slash}DCMI_D3") (class "Default")
      (node (ref "CAMERA") (pin "12") (pinfunction "12_12") (pintype "passive"))
      (node (ref "J1") (pin "P$8") (pinfunction "DAT1_P$8") (pintype "bidirectional"))
      (node (ref "R15") (pin "2") (pinfunction "2_2") (pintype "passive"))
      (node (ref "STMF767IGT6") (pin "118") (pinfunction "PC9_118") (pintype "bidirectional"))
    )
    (net (code "73") (name "/SDIO_D2") (class "Default")
      (node (ref "J1") (pin "P$1") (pinfunction "DAT2_P$1") (pintype "bidirectional"))
      (node (ref "R19") (pin "2") (pinfunction "2_2") (pintype "passive"))
      (node (ref "STMF767IGT6") (pin "139") (pinfunction "PC10_139") (pintype "bidirectional"))
    )
    (net (code "74") (name "/SDIO_D3{slash}DCMI_D4") (class "Default")
      (node (ref "CAMERA") (pin "11") (pinfunction "11_11") (pintype "passive"))
      (node (ref "J1") (pin "P$2") (pinfunction "DAT3_P$2") (pintype "bidirectional"))
      (node (ref "R18") (pin "2") (pinfunction "2_2") (pintype "passive"))
      (node (ref "STMF767IGT6") (pin "140") (pinfunction "PC11_140") (pintype "bidirectional"))
    )
    (net (code "75") (name "/SDIO_SCK") (class "Default")
      (node (ref "J1") (pin "P$5") (pinfunction "CLK_P$5") (pintype "bidirectional"))
      (node (ref "STMF767IGT6") (pin "141") (pinfunction "PC12_141") (pintype "bidirectional"))
    )
    (net (code "76") (name "/SPI2_CS") (class "Default")
      (node (ref "STMF767IGT6") (pin "99") (pinfunction "PD11_99") (pintype "bidirectional"))
      (node (ref "WIFI") (pin "5") (pinfunction "5_5") (pintype "passive"))
    )
    (net (code "77") (name "/SPI2_MISO") (class "Default")
      (node (ref "STMF767IGT6") (pin "94") (pinfunction "PB14_94") (pintype "bidirectional"))
      (node (ref "WIFI") (pin "3") (pinfunction "3_3") (pintype "passive"))
    )
    (net (code "78") (name "/SPI2_MOSI") (class "Default")
      (node (ref "STMF767IGT6") (pin "95") (pinfunction "PB15_95") (pintype "bidirectional"))
      (node (ref "WIFI") (pin "4") (pinfunction "4_4") (pintype "passive"))
    )
    (net (code "79") (name "/SPI2_RESET") (class "Default")
      (node (ref "STMF767IGT6") (pin "100") (pinfunction "PD12_100") (pintype "bidirectional"))
      (node (ref "WIFI") (pin "6") (pinfunction "6_6") (pintype "passive"))
    )
    (net (code "80") (name "/SPI2_SCK") (class "Default")
      (node (ref "STMF767IGT6") (pin "93") (pinfunction "PB13_93") (pintype "bidirectional"))
      (node (ref "WIFI") (pin "2") (pinfunction "2_2") (pintype "passive"))
    )
    (net (code "81") (name "/UART4_RX") (class "Default")
      (node (ref "ADAFRUIT_GPS") (pin "4") (pinfunction "4_4") (pintype "passive"))
      (node (ref "STMF767IGT6") (pin "122") (pinfunction "PA11_122") (pintype "bidirectional"))
    )
    (net (code "82") (name "/UART4_TX") (class "Default")
      (node (ref "ADAFRUIT_GPS") (pin "5") (pinfunction "5_5") (pintype "passive"))
      (node (ref "STMF767IGT6") (pin "123") (pinfunction "PA12_123") (pintype "bidirectional"))
    )
    (net (code "83") (name "/USART1_RX") (class "Default")
      (node (ref "R20") (pin "1") (pinfunction "1_1") (pintype "passive"))
      (node (ref "STMF767IGT6") (pin "121") (pinfunction "PA10_121") (pintype "bidirectional"))
      (node (ref "USB_SERIAL") (pin "25") (pinfunction "RXD_25") (pintype "passive"))
    )
    (net (code "84") (name "/USART1_TX") (class "Default")
      (node (ref "R1") (pin "1") (pinfunction "1_1") (pintype "passive"))
      (node (ref "STMF767IGT6") (pin "120") (pinfunction "PA9_120") (pintype "bidirectional"))
      (node (ref "USB_SERIAL") (pin "26") (pinfunction "TXD_26") (pintype "passive"))
    )
    (net (code "85") (name "/VDD3.3V") (class "Default")
      (node (ref "ACCELEROMETER") (pin "14") (pinfunction "VS_14") (pintype "bidirectional"))
      (node (ref "ACCELEROMETER") (pin "15") (pinfunction "VS_15") (pintype "bidirectional"))
      (node (ref "ADAFRUIT_GPS") (pin "2") (pinfunction "2_2") (pintype "passive"))
      (node (ref "C1") (pin "1") (pinfunction "1_1") (pintype "passive"))
      (node (ref "C10") (pin "1") (pinfunction "1_1") (pintype "passive"))
      (node (ref "C11") (pin "1") (pinfunction "1_1") (pintype "passive"))
      (node (ref "C12") (pin "1") (pinfunction "1_1") (pintype "passive"))
      (node (ref "C13") (pin "1") (pinfunction "1_1") (pintype "passive"))
      (node (ref "C14") (pin "1") (pinfunction "1_1") (pintype "passive"))
      (node (ref "C15") (pin "1") (pinfunction "1_1") (pintype "passive"))
      (node (ref "C16") (pin "1") (pinfunction "1_1") (pintype "passive"))
      (node (ref "C17") (pin "1") (pinfunction "1_1") (pintype "passive"))
      (node (ref "C18") (pin "1") (pinfunction "1_1") (pintype "passive"))
      (node (ref "C19") (pin "1") (pinfunction "1_1") (pintype "passive"))
      (node (ref "C22") (pin "1") (pinfunction "1_1") (pintype "passive"))
      (node (ref "C23") (pin "1") (pinfunction "1_1") (pintype "passive"))
      (node (ref "C24") (pin "1") (pinfunction "1_1") (pintype "passive"))
      (node (ref "C25") (pin "1") (pinfunction "1_1") (pintype "passive"))
      (node (ref "C26") (pin "1") (pinfunction "1_1") (pintype "passive"))
      (node (ref "C27") (pin "1") (pinfunction "1_1") (pintype "passive"))
      (node (ref "C28") (pin "1") (pinfunction "1_1") (pintype "passive"))
      (node (ref "C29") (pin "1") (pinfunction "1_1") (pintype "passive"))
      (node (ref "C41") (pin "2") (pinfunction "2_2") (pintype "passive"))
      (node (ref "C42") (pin "1") (pinfunction "1_1") (pintype "passive"))
      (node (ref "C43") (pin "1") (pinfunction "1_1") (pintype "passive"))
      (node (ref "C44") (pin "1") (pinfunction "1_1") (pintype "passive"))
      (node (ref "C45") (pin "1") (pinfunction "1_1") (pintype "passive"))
      (node (ref "C46") (pin "1") (pinfunction "1_1") (pintype "passive"))
      (node (ref "C47") (pin "1") (pinfunction "1_1") (pintype "passive"))
      (node (ref "C48") (pin "1") (pinfunction "1_1") (pintype "passive"))
      (node (ref "C49") (pin "1") (pinfunction "1_1") (pintype "passive"))
      (node (ref "C51") (pin "1") (pinfunction "1_1") (pintype "passive"))
      (node (ref "C56") (pin "1") (pinfunction "1_1") (pintype "passive"))
      (node (ref "C9") (pin "1") (pinfunction "1_1") (pintype "passive"))
      (node (ref "CAMERA") (pin "2") (pinfunction "2_2") (pintype "passive"))
      (node (ref "IC2") (pin "2") (pinfunction "VOUT_2") (pintype "output"))
      (node (ref "IO_EXPAND") (pin "16") (pinfunction "VCC_16") (pintype "power_in"))
      (node (ref "J1") (pin "P$4") (pinfunction "VDD_P$4") (pintype "power_in"))
      (node (ref "R1") (pin "2") (pinfunction "2_2") (pintype "passive"))
      (node (ref "R10") (pin "1") (pinfunction "1_1") (pintype "passive"))
      (node (ref "R12") (pin "2") (pinfunction "2_2") (pintype "passive"))
      (node (ref "R14") (pin "1") (pinfunction "1_1") (pintype "passive"))
      (node (ref "R15") (pin "1") (pinfunction "1_1") (pintype "passive"))
      (node (ref "R16") (pin "1") (pinfunction "1_1") (pintype "passive"))
      (node (ref "R17") (pin "1") (pinfunction "1_1") (pintype "passive"))
      (node (ref "R18") (pin "1") (pinfunction "1_1") (pintype "passive"))
      (node (ref "R19") (pin "1") (pinfunction "1_1") (pintype "passive"))
      (node (ref "R2") (pin "1") (pinfunction "1_1") (pintype "passive"))
      (node (ref "R20") (pin "2") (pinfunction "2_2") (pintype "passive"))
      (node (ref "R22") (pin "2") (pinfunction "2_2") (pintype "passive"))
      (node (ref "R23") (pin "2") (pinfunction "2_2") (pintype "passive"))
      (node (ref "R24") (pin "1") (pinfunction "1_1") (pintype "passive"))
      (node (ref "R8") (pin "1") (pinfunction "1_1") (pintype "passive"))
      (node (ref "S3") (pin "1") (pinfunction "1_1") (pintype "passive"))
      (node (ref "S3") (pin "2") (pinfunction "2_2") (pintype "passive"))
      (node (ref "SDRAM") (pin "1") (pinfunction "VDD_1") (pintype "power_in"))
      (node (ref "SDRAM") (pin "14") (pinfunction "VDD_14") (pintype "power_in"))
      (node (ref "SDRAM") (pin "27") (pinfunction "VDD_27") (pintype "power_in"))
      (node (ref "SDRAM") (pin "3") (pinfunction "VDDQ_3") (pintype "power_in"))
      (node (ref "SDRAM") (pin "43") (pinfunction "VDDQ_43") (pintype "power_in"))
      (node (ref "SDRAM") (pin "49") (pinfunction "VDDQ_49") (pintype "power_in"))
      (node (ref "SDRAM") (pin "9") (pinfunction "VDDQ_9") (pintype "power_in"))
      (node (ref "STMF767IGT6") (pin "103") (pinfunction "VDD_3_103") (pintype "power_in"))
      (node (ref "STMF767IGT6") (pin "114") (pinfunction "VDDUSB_114") (pintype "power_in"))
      (node (ref "STMF767IGT6") (pin "127") (pinfunction "VDD_4_127") (pintype "power_in"))
      (node (ref "STMF767IGT6") (pin "136") (pinfunction "VDD_5_136") (pintype "power_in"))
      (node (ref "STMF767IGT6") (pin "149") (pinfunction "VDDSDMMC_149") (pintype "power_in"))
      (node (ref "STMF767IGT6") (pin "15") (pinfunction "VDD_2_15") (pintype "power_in"))
      (node (ref "STMF767IGT6") (pin "159") (pinfunction "VDD_6_159") (pintype "power_in"))
      (node (ref "STMF767IGT6") (pin "172") (pinfunction "VDD_172") (pintype "power_in"))
      (node (ref "STMF767IGT6") (pin "23") (pinfunction "VDD_3_23") (pintype "power_in"))
      (node (ref "STMF767IGT6") (pin "36") (pinfunction "VDD_4_36") (pintype "power_in"))
      (node (ref "STMF767IGT6") (pin "49") (pinfunction "VDD_5_49") (pintype "power_in"))
      (node (ref "STMF767IGT6") (pin "6") (pinfunction "VBAT_6") (pintype "power_in"))
      (node (ref "STMF767IGT6") (pin "62") (pinfunction "VDD_6_62") (pintype "power_in"))
      (node (ref "STMF767IGT6") (pin "72") (pinfunction "VDD_7_72") (pintype "power_in"))
      (node (ref "STMF767IGT6") (pin "82") (pinfunction "VDD_82") (pintype "power_in"))
      (node (ref "STMF767IGT6") (pin "91") (pinfunction "VDD_2_91") (pintype "power_in"))
      (node (ref "WIFI") (pin "1") (pinfunction "1_1") (pintype "passive"))
    )
    (net (code "86") (name "/VDDA") (class "Default")
      (node (ref "C39") (pin "1") (pinfunction "1_1") (pintype "passive"))
      (node (ref "C40") (pin "1") (pinfunction "1_1") (pintype "passive"))
      (node (ref "R2") (pin "2") (pinfunction "2_2") (pintype "passive"))
      (node (ref "STMF767IGT6") (pin "39") (pinfunction "VDDA_39") (pintype "power_in"))
    )
    (net (code "87") (name "/WK_UP") (class "Default")
      (node (ref "S3") (pin "3") (pinfunction "3_3") (pintype "passive"))
      (node (ref "S3") (pin "4") (pinfunction "4_4") (pintype "passive"))
      (node (ref "STMF767IGT6") (pin "40") (pinfunction "PA0_40") (pintype "bidirectional"))
    )
    (net (code "88") (name "GND") (class "Default")
      (node (ref "ACCELEROMETER") (pin "3") (pinfunction "COM_3") (pintype "bidirectional"))
      (node (ref "ACCELEROMETER") (pin "5") (pinfunction "COM_5") (pintype "bidirectional"))
      (node (ref "ACCELEROMETER") (pin "6") (pinfunction "COM_6") (pintype "bidirectional"))
      (node (ref "ACCELEROMETER") (pin "7") (pinfunction "COM_7") (pintype "bidirectional"))
      (node (ref "ADAFRUIT_GPS") (pin "3") (pinfunction "3_3") (pintype "passive"))
      (node (ref "C1") (pin "2") (pinfunction "2_2") (pintype "passive"))
      (node (ref "C10") (pin "2") (pinfunction "2_2") (pintype "passive"))
      (node (ref "C11") (pin "2") (pinfunction "2_2") (pintype "passive"))
      (node (ref "C12") (pin "2") (pinfunction "2_2") (pintype "passive"))
      (node (ref "C13") (pin "2") (pinfunction "2_2") (pintype "passive"))
      (node (ref "C14") (pin "2") (pinfunction "2_2") (pintype "passive"))
      (node (ref "C15") (pin "2") (pinfunction "2_2") (pintype "passive"))
      (node (ref "C16") (pin "2") (pinfunction "2_2") (pintype "passive"))
      (node (ref "C17") (pin "2") (pinfunction "2_2") (pintype "passive"))
      (node (ref "C18") (pin "2") (pinfunction "2_2") (pintype "passive"))
      (node (ref "C19") (pin "2") (pinfunction "2_2") (pintype "passive"))
      (node (ref "C2") (pin "2") (pinfunction "2_2") (pintype "passive"))
      (node (ref "C20") (pin "2") (pinfunction "2_2") (pintype "passive"))
      (node (ref "C21") (pin "2") (pinfunction "2_2") (pintype "passive"))
      (node (ref "C22") (pin "2") (pinfunction "2_2") (pintype "passive"))
      (node (ref "C23") (pin "2") (pinfunction "2_2") (pintype "passive"))
      (node (ref "C24") (pin "2") (pinfunction "2_2") (pintype "passive"))
      (node (ref "C25") (pin "2") (pinfunction "2_2") (pintype "passive"))
      (node (ref "C26") (pin "2") (pinfunction "2_2") (pintype "passive"))
      (node (ref "C27") (pin "2") (pinfunction "2_2") (pintype "passive"))
      (node (ref "C28") (pin "2") (pinfunction "2_2") (pintype "passive"))
      (node (ref "C29") (pin "2") (pinfunction "2_2") (pintype "passive"))
      (node (ref "C30") (pin "2") (pinfunction "2_2") (pintype "passive"))
      (node (ref "C31") (pin "2") (pinfunction "2_2") (pintype "passive"))
      (node (ref "C32") (pin "2") (pinfunction "2_2") (pintype "passive"))
      (node (ref "C33") (pin "2") (pinfunction "2_2") (pintype "passive"))
      (node (ref "C34") (pin "2") (pinfunction "2_2") (pintype "passive"))
      (node (ref "C35") (pin "2") (pinfunction "2_2") (pintype "passive"))
      (node (ref "C36") (pin "2") (pinfunction "2_2") (pintype "passive"))
      (node (ref "C37") (pin "2") (pinfunction "2_2") (pintype "passive"))
      (node (ref "C38") (pin "2") (pinfunction "2_2") (pintype "passive"))
      (node (ref "C39") (pin "2") (pinfunction "2_2") (pintype "passive"))
      (node (ref "C40") (pin "2") (pinfunction "2_2") (pintype "passive"))
      (node (ref "C41") (pin "1") (pinfunction "1_1") (pintype "passive"))
      (node (ref "C42") (pin "2") (pinfunction "2_2") (pintype "passive"))
      (node (ref "C43") (pin "2") (pinfunction "2_2") (pintype "passive"))
      (node (ref "C44") (pin "2") (pinfunction "2_2") (pintype "passive"))
      (node (ref "C45") (pin "2") (pinfunction "2_2") (pintype "passive"))
      (node (ref "C46") (pin "2") (pinfunction "2_2") (pintype "passive"))
      (node (ref "C47") (pin "2") (pinfunction "2_2") (pintype "passive"))
      (node (ref "C48") (pin "2") (pinfunction "2_2") (pintype "passive"))
      (node (ref "C49") (pin "2") (pinfunction "2_2") (pintype "passive"))
      (node (ref "C50") (pin "2") (pinfunction "2_2") (pintype "passive"))
      (node (ref "C51") (pin "2") (pinfunction "2_2") (pintype "passive"))
      (node (ref "C52") (pin "2") (pinfunction "2_2") (pintype "passive"))
      (node (ref "C54") (pin "2") (pinfunction "2_2") (pintype "passive"))
      (node (ref "C55") (pin "2") (pinfunction "2_2") (pintype "passive"))
      (node (ref "C56") (pin "2") (pinfunction "2_2") (pintype "passive"))
      (node (ref "C9") (pin "2") (pinfunction "2_2") (pintype "passive"))
      (node (ref "CAMERA") (pin "1") (pinfunction "1_1") (pintype "passive"))
      (node (ref "IC2") (pin "1") (pinfunction "GND_1") (pintype "power_in"))
      (node (ref "IO_EXPAND") (pin "1") (pinfunction "A0_1") (pintype "input"))
      (node (ref "IO_EXPAND") (pin "2") (pinfunction "A1_2") (pintype "input"))
      (node (ref "IO_EXPAND") (pin "3") (pinfunction "A2_3") (pintype "input"))
      (node (ref "IO_EXPAND") (pin "8") (pinfunction "GND_8") (pintype "power_in"))
      (node (ref "J1") (pin "GND0") (pinfunction "SH1_GND0") (pintype "power_in"))
      (node (ref "J1") (pin "GND1") (pinfunction "SH2_GND1") (pintype "power_in"))
      (node (ref "J1") (pin "GND2") (pinfunction "SH3_GND2") (pintype "power_in"))
      (node (ref "J1") (pin "GND3") (pinfunction "SH4_GND3") (pintype "power_in"))
      (node (ref "J1") (pin "GND4") (pinfunction "SH5_GND4") (pintype "power_in"))
      (node (ref "J1") (pin "P$6") (pinfunction "VSS_P$6") (pintype "power_in"))
      (node (ref "LED4") (pin "C") (pinfunction "C_C") (pintype "passive"))
      (node (ref "LED_DISP") (pin "3") (pinfunction "3_3") (pintype "passive"))
      (node (ref "R11") (pin "2") (pinfunction "2_2") (pintype "passive"))
      (node (ref "R13") (pin "2") (pinfunction "2_2") (pintype "passive"))
      (node (ref "R9") (pin "2") (pinfunction "2_2") (pintype "passive"))
      (node (ref "S2") (pin "3") (pinfunction "3_3") (pintype "passive"))
      (node (ref "S2") (pin "4") (pinfunction "4_4") (pintype "passive"))
      (node (ref "SDRAM") (pin "12") (pinfunction "VSSQ_12") (pintype "power_in"))
      (node (ref "SDRAM") (pin "28") (pinfunction "VSS_28") (pintype "power_in"))
      (node (ref "SDRAM") (pin "41") (pinfunction "VSS_41") (pintype "power_in"))
      (node (ref "SDRAM") (pin "46") (pinfunction "VSSQ_46") (pintype "power_in"))
      (node (ref "SDRAM") (pin "52") (pinfunction "VSSQ_52") (pintype "power_in"))
      (node (ref "SDRAM") (pin "54") (pinfunction "VSS_54") (pintype "power_in"))
      (node (ref "SDRAM") (pin "6") (pinfunction "VSSQ_6") (pintype "power_in"))
      (node (ref "STMF767IGT6") (pin "102") (pinfunction "VSS_3_102") (pintype "power_in"))
      (node (ref "STMF767IGT6") (pin "113") (pinfunction "VSS_4_113") (pintype "power_in"))
      (node (ref "STMF767IGT6") (pin "126") (pinfunction "VSS_5_126") (pintype "power_in"))
      (node (ref "STMF767IGT6") (pin "135") (pinfunction "VSS_6_135") (pintype "power_in"))
      (node (ref "STMF767IGT6") (pin "14") (pinfunction "VSS_2_14") (pintype "power_in"))
      (node (ref "STMF767IGT6") (pin "148") (pinfunction "VSS_7_148") (pintype "power_in"))
      (node (ref "STMF767IGT6") (pin "158") (pinfunction "VSS_158") (pintype "power_in"))
      (node (ref "STMF767IGT6") (pin "22") (pinfunction "VSS_3_22") (pintype "power_in"))
      (node (ref "STMF767IGT6") (pin "37") (pinfunction "VSSA_37") (pintype "power_in"))
      (node (ref "STMF767IGT6") (pin "61") (pinfunction "VSS_4_61") (pintype "power_in"))
      (node (ref "STMF767IGT6") (pin "71") (pinfunction "VSS_71") (pintype "power_in"))
      (node (ref "STMF767IGT6") (pin "90") (pinfunction "VSS_2_90") (pintype "power_in"))
      (node (ref "USB_SERIAL") (pin "3") (pinfunction "GND_3") (pintype "passive"))
      (node (ref "WIFI") (pin "7") (pinfunction "7_7") (pintype "passive"))
      (node (ref "X3") (pin "4") (pinfunction "4_4") (pintype "passive"))
      (node (ref "X3") (pin "5") (pinfunction "5_5") (pintype "passive"))
      (node (ref "X3") (pin "M1") (pinfunction "S1_M1") (pintype "passive"))
      (node (ref "X3") (pin "M2") (pinfunction "S2_M2") (pintype "passive"))
      (node (ref "X3") (pin "M3") (pinfunction "S3_M3") (pintype "passive"))
      (node (ref "X3") (pin "M4") (pinfunction "S4_M4") (pintype "passive"))
    )
    (net (code "89") (name "Net-(LED3-PadA)") (class "Default")
      (node (ref "LED3") (pin "A") (pinfunction "A_A") (pintype "passive"))
      (node (ref "R22") (pin "1") (pinfunction "1_1") (pintype "passive"))
    )
    (net (code "90") (name "Net-(LED4-PadA)") (class "Default")
      (node (ref "LED4") (pin "A") (pinfunction "A_A") (pintype "passive"))
      (node (ref "R23") (pin "1") (pinfunction "1_1") (pintype "passive"))
    )
    (net (code "91") (name "Net-(LED_DISP-Pad2)") (class "Default")
      (node (ref "LED_DISP") (pin "2") (pinfunction "2_2") (pintype "passive"))
      (node (ref "R27") (pin "2") (pinfunction "2_2") (pintype "passive"))
    )
    (net (code "92") (name "Net-(R24-Pad2)") (class "Default")
      (node (ref "R24") (pin "2") (pinfunction "2_2") (pintype "passive"))
      (node (ref "S4") (pin "3") (pinfunction "3_3") (pintype "passive"))
      (node (ref "S4") (pin "4") (pinfunction "4_4") (pintype "passive"))
    )
    (net (code "93") (name "Net-(STMF767IGT6A-BYPASS_REG)") (class "Default")
      (node (ref "R13") (pin "1") (pinfunction "1_1") (pintype "passive"))
      (node (ref "STMF767IGT6") (pin "48") (pinfunction "BYPASS_REG_48") (pintype "input"))
    )
    (net (code "94") (name "Net-(STMF767IGT6A-VCAP_1)") (class "Default")
      (node (ref "C34") (pin "1") (pinfunction "1_1") (pintype "passive"))
      (node (ref "STMF767IGT6") (pin "81") (pinfunction "VCAP_1_81") (pintype "power_in"))
    )
    (net (code "95") (name "Net-(STMF767IGT6A-VREF+)") (class "Default")
      (node (ref "C37") (pin "1") (pinfunction "1_1") (pintype "passive"))
      (node (ref "C38") (pin "1") (pinfunction "1_1") (pintype "passive"))
      (node (ref "R10") (pin "2") (pinfunction "2_2") (pintype "passive"))
      (node (ref "STMF767IGT6") (pin "38") (pinfunction "VREF+_38") (pintype "power_in"))
    )
    (net (code "96") (name "Net-(STMF767IGT6B-BOOT0)") (class "Default")
      (node (ref "R9") (pin "1") (pinfunction "1_1") (pintype "passive"))
      (node (ref "S4") (pin "1") (pinfunction "1_1") (pintype "passive"))
      (node (ref "S4") (pin "2") (pinfunction "2_2") (pintype "passive"))
      (node (ref "STMF767IGT6") (pin "166") (pinfunction "BOOT0_166") (pintype "input"))
    )
    (net (code "97") (name "Net-(STMF767IGT6B-PDR_ON)") (class "Default")
      (node (ref "R11") (pin "1") (pinfunction "1_1") (pintype "passive"))
      (node (ref "R12") (pin "1") (pinfunction "1_1") (pintype "passive"))
      (node (ref "STMF767IGT6") (pin "171") (pinfunction "PDR_ON_171") (pintype "passive"))
    )
    (net (code "98") (name "Net-(STMF767IGT6B-VCAP_2)") (class "Default")
      (node (ref "C35") (pin "1") (pinfunction "1_1") (pintype "passive"))
      (node (ref "STMF767IGT6") (pin "125") (pinfunction "VCAP_2_125") (pintype "power_in"))
    )
    (net (code "99") (name "Net-(USB_SERIAL-VDD)") (class "Default")
      (node (ref "C55") (pin "1") (pinfunction "1_1") (pintype "passive"))
      (node (ref "USB_SERIAL") (pin "6") (pinfunction "VDD_6") (pintype "passive"))
    )
    (net (code "100") (name "unconnected-(ACCELEROMETER-NC-Pad1)") (class "Default")
      (node (ref "ACCELEROMETER") (pin "1") (pinfunction "NC_1") (pintype "bidirectional"))
    )
    (net (code "101") (name "unconnected-(ACCELEROMETER-NC-Pad4)") (class "Default")
      (node (ref "ACCELEROMETER") (pin "4") (pinfunction "NC_4") (pintype "bidirectional"))
    )
    (net (code "102") (name "unconnected-(ACCELEROMETER-NC-Pad9)") (class "Default")
      (node (ref "ACCELEROMETER") (pin "9") (pinfunction "NC_9") (pintype "bidirectional"))
    )
    (net (code "103") (name "unconnected-(ACCELEROMETER-NC-Pad11)") (class "Default")
      (node (ref "ACCELEROMETER") (pin "11") (pinfunction "NC_11") (pintype "bidirectional"))
    )
    (net (code "104") (name "unconnected-(ACCELEROMETER-NC-Pad13)") (class "Default")
      (node (ref "ACCELEROMETER") (pin "13") (pinfunction "NC_13") (pintype "bidirectional"))
    )
    (net (code "105") (name "unconnected-(ACCELEROMETER-NC-Pad16)") (class "Default")
      (node (ref "ACCELEROMETER") (pin "16") (pinfunction "NC_16") (pintype "bidirectional"))
    )
    (net (code "106") (name "unconnected-(ACCELEROMETER-ST-Pad2)") (class "Default")
      (node (ref "ACCELEROMETER") (pin "2") (pinfunction "ST_2") (pintype "bidirectional"))
    )
    (net (code "107") (name "unconnected-(ADAFRUIT_GPS-Pad1)") (class "Default")
      (node (ref "ADAFRUIT_GPS") (pin "1") (pinfunction "1_1") (pintype "passive"))
    )
    (net (code "108") (name "unconnected-(ADAFRUIT_GPS-Pad6)") (class "Default")
      (node (ref "ADAFRUIT_GPS") (pin "6") (pinfunction "6_6") (pintype "passive"))
    )
    (net (code "109") (name "unconnected-(ADAFRUIT_GPS-Pad7)") (class "Default")
      (node (ref "ADAFRUIT_GPS") (pin "7") (pinfunction "7_7") (pintype "passive"))
    )
    (net (code "110") (name "unconnected-(ADAFRUIT_GPS-Pad9)") (class "Default")
      (node (ref "ADAFRUIT_GPS") (pin "9") (pinfunction "9_9") (pintype "passive"))
    )
    (net (code "111") (name "unconnected-(IO_EXPANDA-P1-Pad5)") (class "Default")
      (node (ref "IO_EXPAND") (pin "5") (pinfunction "P1_5") (pintype "bidirectional"))
    )
    (net (code "112") (name "unconnected-(IO_EXPANDA-P2-Pad6)") (class "Default")
      (node (ref "IO_EXPAND") (pin "6") (pinfunction "P2_6") (pintype "bidirectional"))
    )
    (net (code "113") (name "unconnected-(IO_EXPANDA-P3-Pad7)") (class "Default")
      (node (ref "IO_EXPAND") (pin "7") (pinfunction "P3_7") (pintype "bidirectional"))
    )
    (net (code "114") (name "unconnected-(IO_EXPANDA-P4-Pad9)") (class "Default")
      (node (ref "IO_EXPAND") (pin "9") (pinfunction "P4_9") (pintype "bidirectional"))
    )
    (net (code "115") (name "unconnected-(IO_EXPANDA-P5-Pad10)") (class "Default")
      (node (ref "IO_EXPAND") (pin "10") (pinfunction "P5_10") (pintype "bidirectional"))
    )
    (net (code "116") (name "unconnected-(IO_EXPANDA-P6-Pad11)") (class "Default")
      (node (ref "IO_EXPAND") (pin "11") (pinfunction "P6_11") (pintype "bidirectional"))
    )
    (net (code "117") (name "unconnected-(IO_EXPANDA-P7-Pad12)") (class "Default")
      (node (ref "IO_EXPAND") (pin "12") (pinfunction "P7_12") (pintype "bidirectional"))
    )
    (net (code "118") (name "unconnected-(SDRAM-NC-Pad40)") (class "Default")
      (node (ref "SDRAM") (pin "40") (pinfunction "NC_40") (pintype "no_connect"))
    )
    (net (code "119") (name "unconnected-(STMF767IGT6A-PA4-Pad50)") (class "Default")
      (node (ref "STMF767IGT6") (pin "50") (pinfunction "PA4_50") (pintype "bidirectional"))
    )
    (net (code "120") (name "unconnected-(STMF767IGT6A-PA5-Pad51)") (class "Default")
      (node (ref "STMF767IGT6") (pin "51") (pinfunction "PA5_51") (pintype "bidirectional"))
    )
    (net (code "121") (name "unconnected-(STMF767IGT6A-PA7-Pad53)") (class "Default")
      (node (ref "STMF767IGT6") (pin "53") (pinfunction "PA7_53") (pintype "bidirectional"))
    )
    (net (code "122") (name "unconnected-(STMF767IGT6A-PB0-Pad56)") (class "Default")
      (node (ref "STMF767IGT6") (pin "56") (pinfunction "PB0_56") (pintype "bidirectional"))
    )
    (net (code "123") (name "unconnected-(STMF767IGT6A-PB1-Pad57)") (class "Default")
      (node (ref "STMF767IGT6") (pin "57") (pinfunction "PB1_57") (pintype "bidirectional"))
    )
    (net (code "124") (name "unconnected-(STMF767IGT6A-PB2-Pad58)") (class "Default")
      (node (ref "STMF767IGT6") (pin "58") (pinfunction "PB2_58") (pintype "bidirectional"))
    )
    (net (code "125") (name "unconnected-(STMF767IGT6A-PB10-Pad79)") (class "Default")
      (node (ref "STMF767IGT6") (pin "79") (pinfunction "PB10_79") (pintype "bidirectional"))
    )
    (net (code "126") (name "unconnected-(STMF767IGT6A-PB11-Pad80)") (class "Default")
      (node (ref "STMF767IGT6") (pin "80") (pinfunction "PB11_80") (pintype "bidirectional"))
    )
    (net (code "127") (name "unconnected-(STMF767IGT6A-PC1-Pad33)") (class "Default")
      (node (ref "STMF767IGT6") (pin "33") (pinfunction "PC1_33") (pintype "bidirectional"))
    )
    (net (code "128") (name "unconnected-(STMF767IGT6A-PC4-Pad54)") (class "Default")
      (node (ref "STMF767IGT6") (pin "54") (pinfunction "PC4_54") (pintype "bidirectional"))
    )
    (net (code "129") (name "unconnected-(STMF767IGT6A-PC13-Pad8)") (class "Default")
      (node (ref "STMF767IGT6") (pin "8") (pinfunction "PC13_8") (pintype "bidirectional"))
    )
    (net (code "130") (name "unconnected-(STMF767IGT6A-PE2-Pad1)") (class "Default")
      (node (ref "STMF767IGT6") (pin "1") (pinfunction "PE2_1") (pintype "bidirectional"))
    )
    (net (code "131") (name "unconnected-(STMF767IGT6A-PE3-Pad2)") (class "Default")
      (node (ref "STMF767IGT6") (pin "2") (pinfunction "PE3_2") (pintype "bidirectional"))
    )
    (net (code "132") (name "unconnected-(STMF767IGT6A-PE4-Pad3)") (class "Default")
      (node (ref "STMF767IGT6") (pin "3") (pinfunction "PE4_3") (pintype "bidirectional"))
    )
    (net (code "133") (name "unconnected-(STMF767IGT6A-PE5-Pad4)") (class "Default")
      (node (ref "STMF767IGT6") (pin "4") (pinfunction "PE5_4") (pintype "bidirectional"))
    )
    (net (code "134") (name "unconnected-(STMF767IGT6A-PE6-Pad5)") (class "Default")
      (node (ref "STMF767IGT6") (pin "5") (pinfunction "PE6_5") (pintype "bidirectional"))
    )
    (net (code "135") (name "unconnected-(STMF767IGT6A-PF6-Pad24)") (class "Default")
      (node (ref "STMF767IGT6") (pin "24") (pinfunction "PF6_24") (pintype "bidirectional"))
    )
    (net (code "136") (name "unconnected-(STMF767IGT6A-PF7-Pad25)") (class "Default")
      (node (ref "STMF767IGT6") (pin "25") (pinfunction "PF7_25") (pintype "bidirectional"))
    )
    (net (code "137") (name "unconnected-(STMF767IGT6A-PF8-Pad26)") (class "Default")
      (node (ref "STMF767IGT6") (pin "26") (pinfunction "PF8_26") (pintype "bidirectional"))
    )
    (net (code "138") (name "unconnected-(STMF767IGT6A-PF9-Pad27)") (class "Default")
      (node (ref "STMF767IGT6") (pin "27") (pinfunction "PF9_27") (pintype "bidirectional"))
    )
    (net (code "139") (name "unconnected-(STMF767IGT6A-PF10-Pad28)") (class "Default")
      (node (ref "STMF767IGT6") (pin "28") (pinfunction "PF10_28") (pintype "bidirectional"))
    )
    (net (code "140") (name "unconnected-(STMF767IGT6A-PH2-Pad43)") (class "Default")
      (node (ref "STMF767IGT6") (pin "43") (pinfunction "PH2_43") (pintype "bidirectional"))
    )
    (net (code "141") (name "unconnected-(STMF767IGT6A-PH3-Pad44)") (class "Default")
      (node (ref "STMF767IGT6") (pin "44") (pinfunction "PH3_44") (pintype "bidirectional"))
    )
    (net (code "142") (name "unconnected-(STMF767IGT6A-PH6-Pad83)") (class "Default")
      (node (ref "STMF767IGT6") (pin "83") (pinfunction "PH6_83") (pintype "bidirectional"))
    )
    (net (code "143") (name "unconnected-(STMF767IGT6A-PH7-Pad84)") (class "Default")
      (node (ref "STMF767IGT6") (pin "84") (pinfunction "PH7_84") (pintype "bidirectional"))
    )
    (net (code "144") (name "unconnected-(STMF767IGT6A-PH9-Pad86)") (class "Default")
      (node (ref "STMF767IGT6") (pin "86") (pinfunction "PH9_86") (pintype "bidirectional"))
    )
    (net (code "145") (name "unconnected-(STMF767IGT6A-PH10-Pad87)") (class "Default")
      (node (ref "STMF767IGT6") (pin "87") (pinfunction "PH10_87") (pintype "bidirectional"))
    )
    (net (code "146") (name "unconnected-(STMF767IGT6A-PH11-Pad88)") (class "Default")
      (node (ref "STMF767IGT6") (pin "88") (pinfunction "PH11_88") (pintype "bidirectional"))
    )
    (net (code "147") (name "unconnected-(STMF767IGT6A-PI8-Pad7)") (class "Default")
      (node (ref "STMF767IGT6") (pin "7") (pinfunction "PI8_7") (pintype "bidirectional"))
    )
    (net (code "148") (name "unconnected-(STMF767IGT6A-PI9-Pad11)") (class "Default")
      (node (ref "STMF767IGT6") (pin "11") (pinfunction "PI9_11") (pintype "bidirectional"))
    )
    (net (code "149") (name "unconnected-(STMF767IGT6A-PI10-Pad12)") (class "Default")
      (node (ref "STMF767IGT6") (pin "12") (pinfunction "PI10_12") (pintype "bidirectional"))
    )
    (net (code "150") (name "unconnected-(STMF767IGT6A-PI11-Pad13)") (class "Default")
      (node (ref "STMF767IGT6") (pin "13") (pinfunction "PI11_13") (pintype "bidirectional"))
    )
    (net (code "151") (name "unconnected-(STMF767IGT6B-PA13-Pad124)") (class "Default")
      (node (ref "STMF767IGT6") (pin "124") (pinfunction "PA13_124") (pintype "bidirectional"))
    )
    (net (code "152") (name "unconnected-(STMF767IGT6B-PA14-Pad137)") (class "Default")
      (node (ref "STMF767IGT6") (pin "137") (pinfunction "PA14_137") (pintype "bidirectional"))
    )
    (net (code "153") (name "unconnected-(STMF767IGT6B-PB5-Pad163)") (class "Default")
      (node (ref "STMF767IGT6") (pin "163") (pinfunction "PB5_163") (pintype "bidirectional"))
    )
    (net (code "154") (name "unconnected-(STMF767IGT6B-PB6-Pad164)") (class "Default")
      (node (ref "STMF767IGT6") (pin "164") (pinfunction "PB6_164") (pintype "bidirectional"))
    )
    (net (code "155") (name "unconnected-(STMF767IGT6B-PD4-Pad146)") (class "Default")
      (node (ref "STMF767IGT6") (pin "146") (pinfunction "PD4_146") (pintype "bidirectional"))
    )
    (net (code "156") (name "unconnected-(STMF767IGT6B-PD5-Pad147)") (class "Default")
      (node (ref "STMF767IGT6") (pin "147") (pinfunction "PD5_147") (pintype "bidirectional"))
    )
    (net (code "157") (name "unconnected-(STMF767IGT6B-PD6-Pad150)") (class "Default")
      (node (ref "STMF767IGT6") (pin "150") (pinfunction "PD6_150") (pintype "bidirectional"))
    )
    (net (code "158") (name "unconnected-(STMF767IGT6B-PD7-Pad151)") (class "Default")
      (node (ref "STMF767IGT6") (pin "151") (pinfunction "PD7_151") (pintype "bidirectional"))
    )
    (net (code "159") (name "unconnected-(STMF767IGT6B-PD13-Pad101)") (class "Default")
      (node (ref "STMF767IGT6") (pin "101") (pinfunction "PD13_101") (pintype "bidirectional"))
    )
    (net (code "160") (name "unconnected-(STMF767IGT6B-PG3-Pad107)") (class "Default")
      (node (ref "STMF767IGT6") (pin "107") (pinfunction "PG3_107") (pintype "bidirectional"))
    )
    (net (code "161") (name "unconnected-(STMF767IGT6B-PG6-Pad110)") (class "Default")
      (node (ref "STMF767IGT6") (pin "110") (pinfunction "PG6_110") (pintype "bidirectional"))
    )
    (net (code "162") (name "unconnected-(STMF767IGT6B-PG7-Pad111)") (class "Default")
      (node (ref "STMF767IGT6") (pin "111") (pinfunction "PG7_111") (pintype "bidirectional"))
    )
    (net (code "163") (name "unconnected-(STMF767IGT6B-PG9-Pad152)") (class "Default")
      (node (ref "STMF767IGT6") (pin "152") (pinfunction "PG9_152") (pintype "bidirectional"))
    )
    (net (code "164") (name "unconnected-(STMF767IGT6B-PG10-Pad153)") (class "Default")
      (node (ref "STMF767IGT6") (pin "153") (pinfunction "PG10_153") (pintype "bidirectional"))
    )
    (net (code "165") (name "unconnected-(STMF767IGT6B-PG11-Pad154)") (class "Default")
      (node (ref "STMF767IGT6") (pin "154") (pinfunction "PG11_154") (pintype "bidirectional"))
    )
    (net (code "166") (name "unconnected-(STMF767IGT6B-PG12-Pad155)") (class "Default")
      (node (ref "STMF767IGT6") (pin "155") (pinfunction "PG12_155") (pintype "bidirectional"))
    )
    (net (code "167") (name "unconnected-(STMF767IGT6B-PG13-Pad156)") (class "Default")
      (node (ref "STMF767IGT6") (pin "156") (pinfunction "PG13_156") (pintype "bidirectional"))
    )
    (net (code "168") (name "unconnected-(STMF767IGT6B-PG14-Pad157)") (class "Default")
      (node (ref "STMF767IGT6") (pin "157") (pinfunction "PG14_157") (pintype "bidirectional"))
    )
    (net (code "169") (name "unconnected-(STMF767IGT6B-PH12-Pad89)") (class "Default")
      (node (ref "STMF767IGT6") (pin "89") (pinfunction "PH12_89") (pintype "bidirectional"))
    )
    (net (code "170") (name "unconnected-(STMF767IGT6B-PH13-Pad128)") (class "Default")
      (node (ref "STMF767IGT6") (pin "128") (pinfunction "PH13_128") (pintype "bidirectional"))
    )
    (net (code "171") (name "unconnected-(STMF767IGT6B-PH14-Pad129)") (class "Default")
      (node (ref "STMF767IGT6") (pin "129") (pinfunction "PH14_129") (pintype "bidirectional"))
    )
    (net (code "172") (name "unconnected-(STMF767IGT6B-PI0-Pad131)") (class "Default")
      (node (ref "STMF767IGT6") (pin "131") (pinfunction "PI0_131") (pintype "bidirectional"))
    )
    (net (code "173") (name "unconnected-(STMF767IGT6B-PI1-Pad132)") (class "Default")
      (node (ref "STMF767IGT6") (pin "132") (pinfunction "PI1_132") (pintype "bidirectional"))
    )
    (net (code "174") (name "unconnected-(STMF767IGT6B-PI2-Pad133)") (class "Default")
      (node (ref "STMF767IGT6") (pin "133") (pinfunction "PI2_133") (pintype "bidirectional"))
    )
    (net (code "175") (name "unconnected-(STMF767IGT6B-PI3-Pad134)") (class "Default")
      (node (ref "STMF767IGT6") (pin "134") (pinfunction "PI3_134") (pintype "bidirectional"))
    )
    (net (code "176") (name "unconnected-(STMF767IGT6B-PI4-Pad173)") (class "Default")
      (node (ref "STMF767IGT6") (pin "173") (pinfunction "PI4_173") (pintype "bidirectional"))
    )
    (net (code "177") (name "unconnected-(STMF767IGT6B-PI5-Pad174)") (class "Default")
      (node (ref "STMF767IGT6") (pin "174") (pinfunction "PI5_174") (pintype "bidirectional"))
    )
    (net (code "178") (name "unconnected-(STMF767IGT6B-PI6-Pad175)") (class "Default")
      (node (ref "STMF767IGT6") (pin "175") (pinfunction "PI6_175") (pintype "bidirectional"))
    )
    (net (code "179") (name "unconnected-(USB_SERIAL-CTS-Pad23)") (class "Default")
      (node (ref "USB_SERIAL") (pin "23") (pinfunction "CTS_23") (pintype "passive"))
    )
    (net (code "180") (name "unconnected-(USB_SERIAL-DCD-Pad1)") (class "Default")
      (node (ref "USB_SERIAL") (pin "1") (pinfunction "DCD_1") (pintype "passive"))
    )
    (net (code "181") (name "unconnected-(USB_SERIAL-DSR-Pad27)") (class "Default")
      (node (ref "USB_SERIAL") (pin "27") (pinfunction "DSR_27") (pintype "passive"))
    )
    (net (code "182") (name "unconnected-(USB_SERIAL-DTR-Pad28)") (class "Default")
      (node (ref "USB_SERIAL") (pin "28") (pinfunction "DTR_28") (pintype "passive"))
    )
    (net (code "183") (name "unconnected-(USB_SERIAL-HEAT_TAB-Pad29)") (class "Default")
      (node (ref "USB_SERIAL") (pin "29") (pinfunction "HEAT_TAB_29") (pintype "passive"))
    )
    (net (code "184") (name "unconnected-(USB_SERIAL-NC-Pad22)") (class "Default")
      (node (ref "USB_SERIAL") (pin "22") (pinfunction "NC_22") (pintype "passive"))
    )
    (net (code "185") (name "unconnected-(USB_SERIAL-NC_2-Pad10)") (class "Default")
      (node (ref "USB_SERIAL") (pin "10") (pinfunction "NC_2_10") (pintype "passive"))
    )
    (net (code "186") (name "unconnected-(USB_SERIAL-NC_3-Pad13)") (class "Default")
      (node (ref "USB_SERIAL") (pin "13") (pinfunction "NC_3_13") (pintype "passive"))
    )
    (net (code "187") (name "unconnected-(USB_SERIAL-NC_4-Pad14)") (class "Default")
      (node (ref "USB_SERIAL") (pin "14") (pinfunction "NC_4_14") (pintype "passive"))
    )
    (net (code "188") (name "unconnected-(USB_SERIAL-NC_5-Pad15)") (class "Default")
      (node (ref "USB_SERIAL") (pin "15") (pinfunction "NC_5_15") (pintype "passive"))
    )
    (net (code "189") (name "unconnected-(USB_SERIAL-NC_6-Pad16)") (class "Default")
      (node (ref "USB_SERIAL") (pin "16") (pinfunction "NC_6_16") (pintype "passive"))
    )
    (net (code "190") (name "unconnected-(USB_SERIAL-NC_7-Pad17)") (class "Default")
      (node (ref "USB_SERIAL") (pin "17") (pinfunction "NC_7_17") (pintype "passive"))
    )
    (net (code "191") (name "unconnected-(USB_SERIAL-NC_8-Pad18)") (class "Default")
      (node (ref "USB_SERIAL") (pin "18") (pinfunction "NC_8_18") (pintype "passive"))
    )
    (net (code "192") (name "unconnected-(USB_SERIAL-NC_9-Pad19)") (class "Default")
      (node (ref "USB_SERIAL") (pin "19") (pinfunction "NC_9_19") (pintype "passive"))
    )
    (net (code "193") (name "unconnected-(USB_SERIAL-NC_10-Pad20)") (class "Default")
      (node (ref "USB_SERIAL") (pin "20") (pinfunction "NC_10_20") (pintype "passive"))
    )
    (net (code "194") (name "unconnected-(USB_SERIAL-NC_11-Pad21)") (class "Default")
      (node (ref "USB_SERIAL") (pin "21") (pinfunction "NC_11_21") (pintype "passive"))
    )
    (net (code "195") (name "unconnected-(USB_SERIAL-RI-Pad2)") (class "Default")
      (node (ref "USB_SERIAL") (pin "2") (pinfunction "RI_2") (pintype "passive"))
    )
    (net (code "196") (name "unconnected-(USB_SERIAL-RTS-Pad24)") (class "Default")
      (node (ref "USB_SERIAL") (pin "24") (pinfunction "RTS_24") (pintype "passive"))
    )
    (net (code "197") (name "unconnected-(USB_SERIAL-SUSPEND-Pad12)") (class "Default")
      (node (ref "USB_SERIAL") (pin "12") (pinfunction "SUSPEND_12") (pintype "passive"))
    )
    (net (code "198") (name "unconnected-(USB_SERIAL-~{RST}-Pad9)") (class "Default")
      (node (ref "USB_SERIAL") (pin "9") (pinfunction "~{RST}_9") (pintype "passive"))
    )
    (net (code "199") (name "unconnected-(USB_SERIAL-~{SUSPEND}-Pad11)") (class "Default")
      (node (ref "USB_SERIAL") (pin "11") (pinfunction "~{SUSPEND}_11") (pintype "passive"))
    )
  )
)
